# Motor_Board.net
KiCad netlist of a schematic drawn in EAGLE
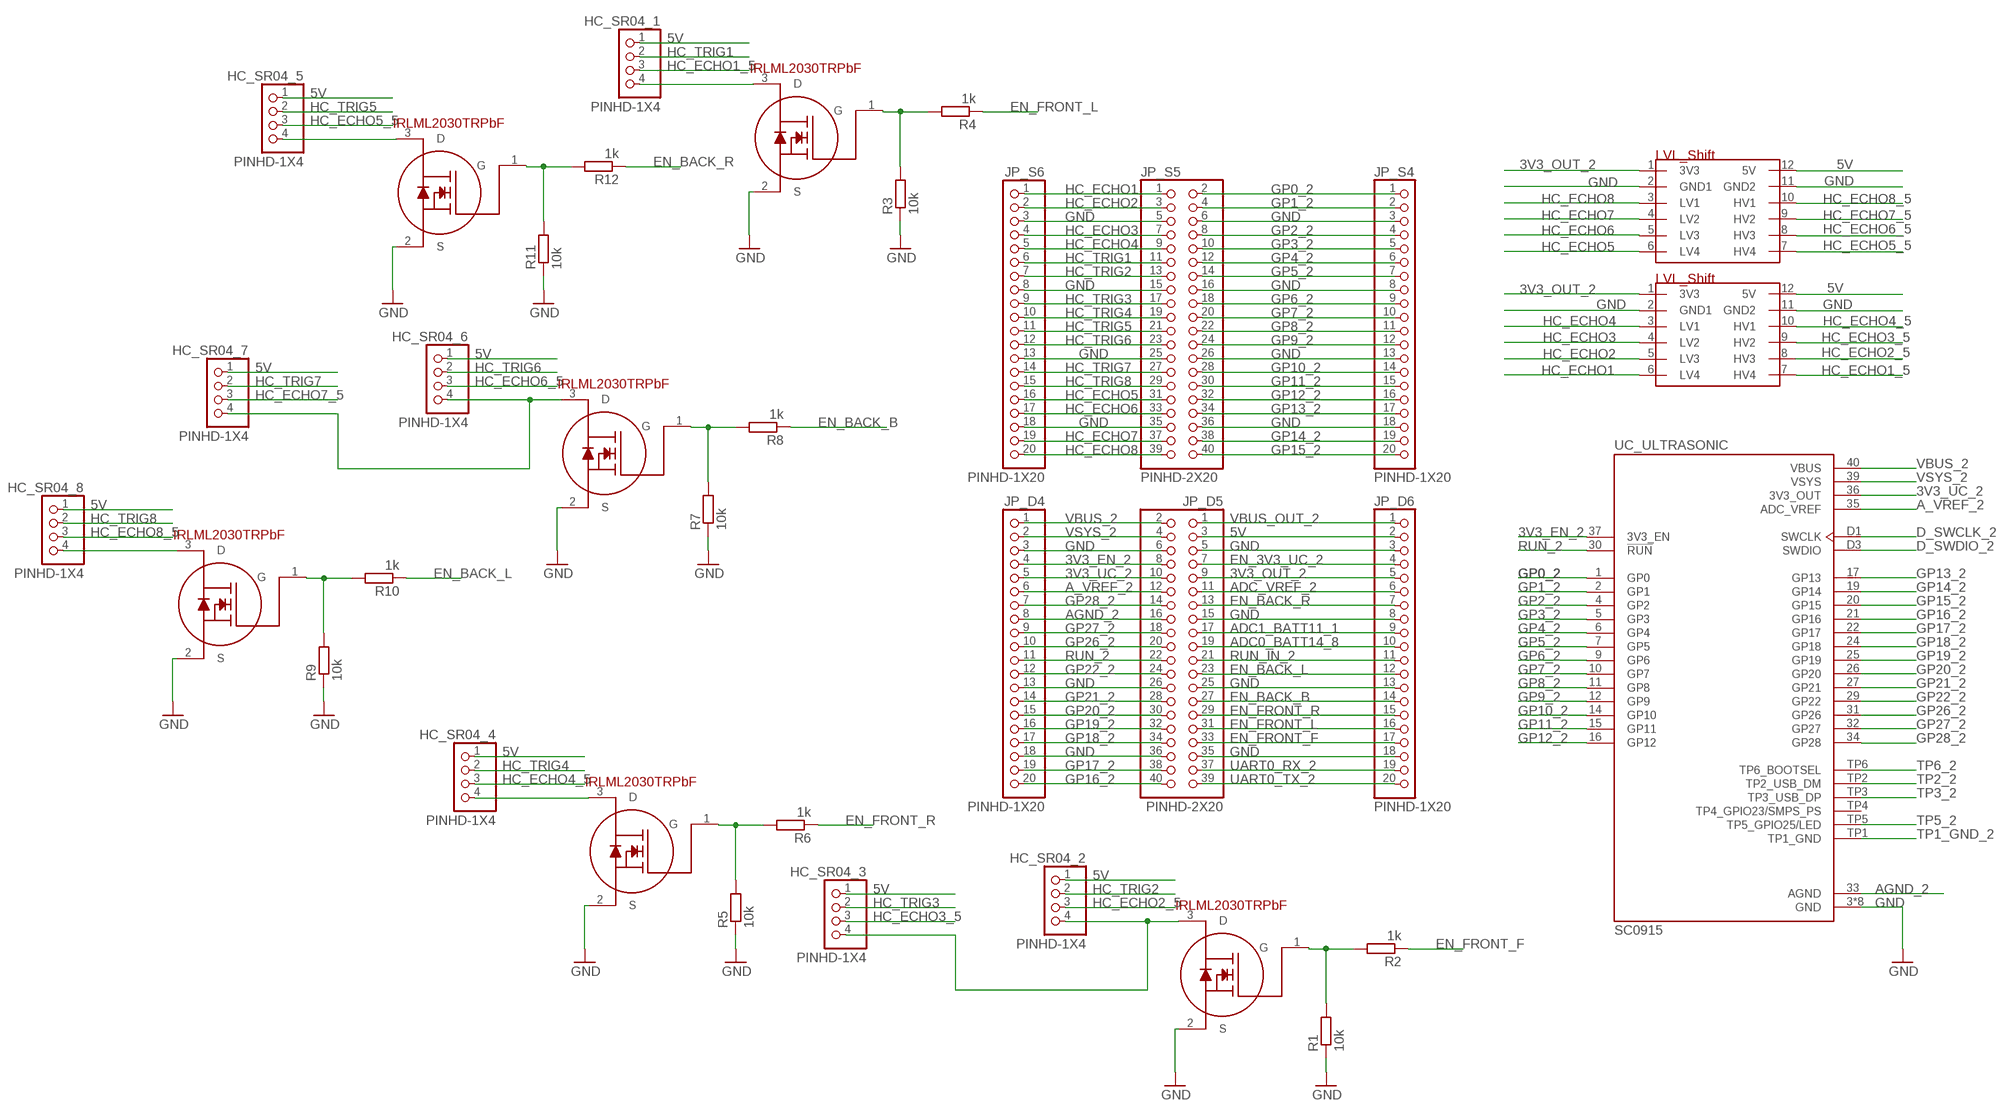
[diagram p0: schematic, sheet 1, part 1 of 2]
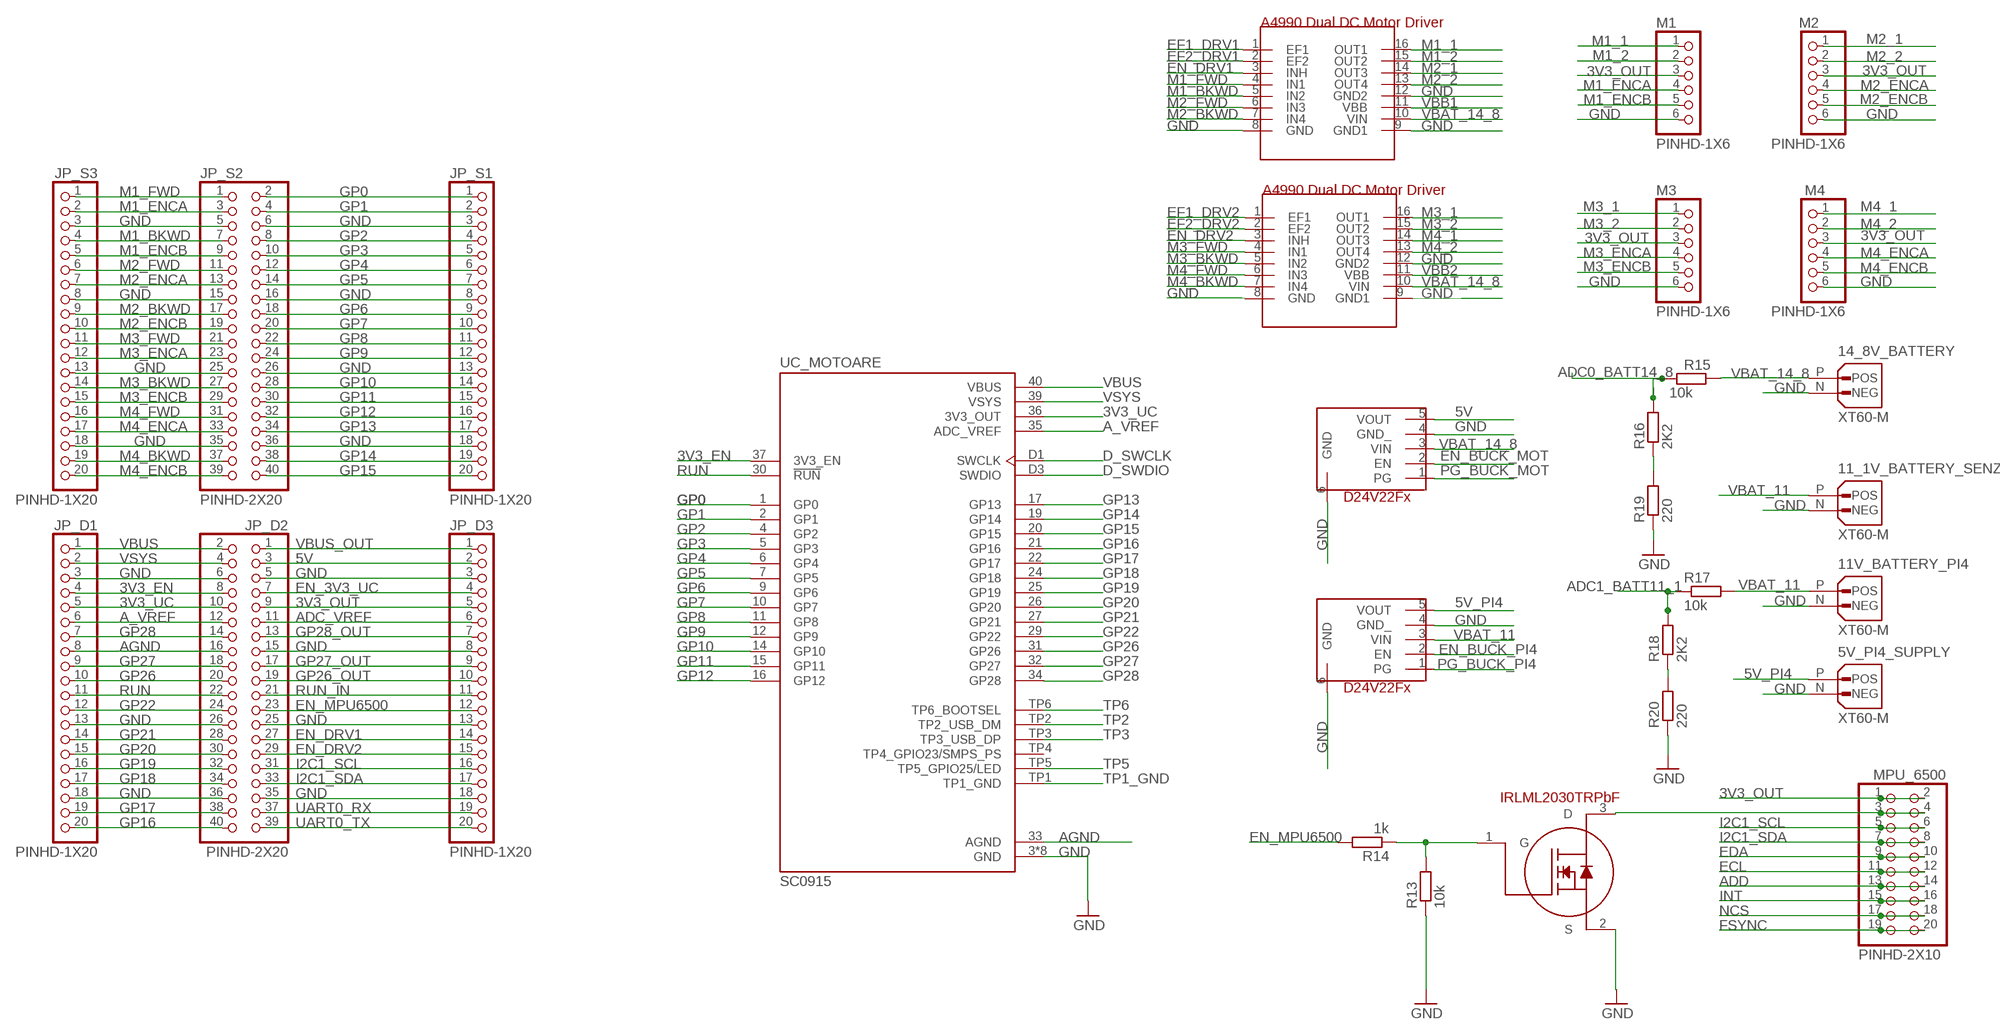
[diagram p1: schematic, sheet 1, part 2 of 2]

(export (version "E")
  (design (tool "Eeschema 10.0.6"))
  (components
    (comp (ref "5V_PI4_SUPPLY")
      (value "XT60-M")
      (footprint "eagle-import:AMASS_XT60-M")
      (fields (field (name "MANUFACTURER") "AMASS"))
      (libsource (lib "eagle-import") (part "XT60-M"))
    )
    (comp (ref "11V_BATTERY_PI4")
      (value "XT60-M")
      (footprint "eagle-import:AMASS_XT60-M")
      (fields (field (name "MANUFACTURER") "AMASS"))
      (libsource (lib "eagle-import") (part "XT60-M"))
    )
    (comp (ref "11_1V_BATTERY_SENZ")
      (value "XT60-M")
      (footprint "eagle-import:AMASS_XT60-M")
      (fields (field (name "MANUFACTURER") "AMASS"))
      (libsource (lib "eagle-import") (part "XT60-M"))
    )
    (comp (ref "14_8V_BATTERY")
      (value "XT60-M")
      (footprint "eagle-import:AMASS_XT60-M")
      (fields (field (name "MANUFACTURER") "AMASS"))
      (libsource (lib "eagle-import") (part "XT60-M"))
    )
    (comp (ref "BUCK_5V")
      (value "POLOLU_BUCK_CONVERTER")
      (footprint "eagle-import:POLOLU_BUCK_FOOTPRINT")
      (libsource (lib "eagle-import") (part "POLOLU_BUCK_CONVERTER"))
    )
    (comp (ref "BUCK_5V1")
      (value "POLOLU_BUCK_CONVERTER")
      (footprint "eagle-import:POLOLU_BUCK_FOOTPRINT")
      (libsource (lib "eagle-import") (part "POLOLU_BUCK_CONVERTER"))
    )
    (comp (ref "DRV1")
      (value "A4990_DUAL")
      (footprint "eagle-import:A4990_FOOTPRINT")
      (libsource (lib "eagle-import") (part "A4990_DUAL"))
    )
    (comp (ref "DRV2")
      (value "A4990_DUAL")
      (footprint "eagle-import:A4990_FOOTPRINT")
      (libsource (lib "eagle-import") (part "A4990_DUAL"))
    )
    (comp (ref "HC_SR04_1")
      (value "PINHD-1X4")
      (footprint "eagle-import:1X04")
      (libsource (lib "eagle-import") (part "PINHD-1X4"))
    )
    (comp (ref "HC_SR04_2")
      (value "PINHD-1X4")
      (footprint "eagle-import:1X04")
      (libsource (lib "eagle-import") (part "PINHD-1X4"))
    )
    (comp (ref "HC_SR04_3")
      (value "PINHD-1X4")
      (footprint "eagle-import:1X04")
      (libsource (lib "eagle-import") (part "PINHD-1X4"))
    )
    (comp (ref "HC_SR04_4")
      (value "PINHD-1X4")
      (footprint "eagle-import:1X04")
      (libsource (lib "eagle-import") (part "PINHD-1X4"))
    )
    (comp (ref "HC_SR04_5")
      (value "PINHD-1X4")
      (footprint "eagle-import:1X04")
      (libsource (lib "eagle-import") (part "PINHD-1X4"))
    )
    (comp (ref "HC_SR04_6")
      (value "PINHD-1X4")
      (footprint "eagle-import:1X04")
      (libsource (lib "eagle-import") (part "PINHD-1X4"))
    )
    (comp (ref "HC_SR04_7")
      (value "PINHD-1X4")
      (footprint "eagle-import:1X04")
      (libsource (lib "eagle-import") (part "PINHD-1X4"))
    )
    (comp (ref "HC_SR04_8")
      (value "PINHD-1X4")
      (footprint "eagle-import:1X04")
      (libsource (lib "eagle-import") (part "PINHD-1X4"))
    )
    (comp (ref "JP_D1")
      (value "PINHD-1X20")
      (footprint "eagle-import:1X20")
      (libsource (lib "eagle-import") (part "PINHD-1X20"))
    )
    (comp (ref "JP_D2")
      (value "PINHD-2X20")
      (footprint "eagle-import:2X20")
      (libsource (lib "eagle-import") (part "PINHD-2X20"))
    )
    (comp (ref "JP_D3")
      (value "PINHD-1X20")
      (footprint "eagle-import:1X20")
      (libsource (lib "eagle-import") (part "PINHD-1X20"))
    )
    (comp (ref "JP_D4")
      (value "PINHD-1X20")
      (footprint "eagle-import:1X20")
      (libsource (lib "eagle-import") (part "PINHD-1X20"))
    )
    (comp (ref "JP_D5")
      (value "PINHD-2X20")
      (footprint "eagle-import:2X20")
      (libsource (lib "eagle-import") (part "PINHD-2X20"))
    )
    (comp (ref "JP_D6")
      (value "PINHD-1X20")
      (footprint "eagle-import:1X20")
      (libsource (lib "eagle-import") (part "PINHD-1X20"))
    )
    (comp (ref "JP_S1")
      (value "PINHD-1X20")
      (footprint "eagle-import:1X20")
      (libsource (lib "eagle-import") (part "PINHD-1X20"))
    )
    (comp (ref "JP_S2")
      (value "PINHD-2X20")
      (footprint "eagle-import:2X20")
      (libsource (lib "eagle-import") (part "PINHD-2X20"))
    )
    (comp (ref "JP_S3")
      (value "PINHD-1X20")
      (footprint "eagle-import:1X20")
      (libsource (lib "eagle-import") (part "PINHD-1X20"))
    )
    (comp (ref "JP_S4")
      (value "PINHD-1X20")
      (footprint "eagle-import:1X20")
      (libsource (lib "eagle-import") (part "PINHD-1X20"))
    )
    (comp (ref "JP_S5")
      (value "PINHD-2X20")
      (footprint "eagle-import:2X20")
      (libsource (lib "eagle-import") (part "PINHD-2X20"))
    )
    (comp (ref "JP_S6")
      (value "PINHD-1X20")
      (footprint "eagle-import:1X20")
      (libsource (lib "eagle-import") (part "PINHD-1X20"))
    )
    (comp (ref "M1")
      (value "PINHD-1X6")
      (footprint "eagle-import:1X06")
      (libsource (lib "eagle-import") (part "PINHD-1X6"))
    )
    (comp (ref "M2")
      (value "PINHD-1X6")
      (footprint "eagle-import:1X06")
      (libsource (lib "eagle-import") (part "PINHD-1X6"))
    )
    (comp (ref "M3")
      (value "PINHD-1X6")
      (footprint "eagle-import:1X06")
      (libsource (lib "eagle-import") (part "PINHD-1X6"))
    )
    (comp (ref "M4")
      (value "PINHD-1X6")
      (footprint "eagle-import:1X06")
      (libsource (lib "eagle-import") (part "PINHD-1X6"))
    )
    (comp (ref "MPU_6500")
      (value "PINHD-2X10")
      (footprint "eagle-import:2X10")
      (libsource (lib "eagle-import") (part "PINHD-2X10"))
    )
    (comp (ref "R1")
      (value "10k")
      (footprint "eagle-import:R0805")
      (libsource (lib "eagle-import") (part "R-EU_R0805"))
    )
    (comp (ref "R2")
      (value "1k")
      (footprint "eagle-import:R0805")
      (libsource (lib "eagle-import") (part "R-EU_R0805"))
    )
    (comp (ref "R3")
      (value "10k")
      (footprint "eagle-import:R0805")
      (libsource (lib "eagle-import") (part "R-EU_R0805"))
    )
    (comp (ref "R4")
      (value "1k")
      (footprint "eagle-import:R0805")
      (libsource (lib "eagle-import") (part "R-EU_R0805"))
    )
    (comp (ref "R5")
      (value "10k")
      (footprint "eagle-import:R0805")
      (libsource (lib "eagle-import") (part "R-EU_R0805"))
    )
    (comp (ref "R6")
      (value "1k")
      (footprint "eagle-import:R0805")
      (libsource (lib "eagle-import") (part "R-EU_R0805"))
    )
    (comp (ref "R7")
      (value "10k")
      (footprint "eagle-import:R0805")
      (libsource (lib "eagle-import") (part "R-EU_R0805"))
    )
    (comp (ref "R8")
      (value "1k")
      (footprint "eagle-import:R0805")
      (libsource (lib "eagle-import") (part "R-EU_R0805"))
    )
    (comp (ref "R9")
      (value "10k")
      (footprint "eagle-import:R0805")
      (libsource (lib "eagle-import") (part "R-EU_R0805"))
    )
    (comp (ref "R10")
      (value "1k")
      (footprint "eagle-import:R0805")
      (libsource (lib "eagle-import") (part "R-EU_R0805"))
    )
    (comp (ref "R11")
      (value "10k")
      (footprint "eagle-import:R0805")
      (libsource (lib "eagle-import") (part "R-EU_R0805"))
    )
    (comp (ref "R12")
      (value "1k")
      (footprint "eagle-import:R0805")
      (libsource (lib "eagle-import") (part "R-EU_R0805"))
    )
    (comp (ref "R13")
      (value "10k")
      (footprint "eagle-import:R0805")
      (libsource (lib "eagle-import") (part "R-EU_R0805"))
    )
    (comp (ref "R14")
      (value "1k")
      (footprint "eagle-import:R0805")
      (libsource (lib "eagle-import") (part "R-EU_R0805"))
    )
    (comp (ref "R15")
      (value "10k")
      (footprint "eagle-import:R0805")
      (libsource (lib "eagle-import") (part "R-EU_R0805"))
    )
    (comp (ref "R16")
      (value "2K2")
      (footprint "eagle-import:R0805")
      (libsource (lib "eagle-import") (part "R-EU_R0805"))
    )
    (comp (ref "R17")
      (value "10k")
      (footprint "eagle-import:R0805")
      (libsource (lib "eagle-import") (part "R-EU_R0805"))
    )
    (comp (ref "R18")
      (value "2K2")
      (footprint "eagle-import:R0805")
      (libsource (lib "eagle-import") (part "R-EU_R0805"))
    )
    (comp (ref "R19")
      (value "220")
      (footprint "eagle-import:R0805")
      (libsource (lib "eagle-import") (part "R-EU_R0805"))
    )
    (comp (ref "R20")
      (value "220")
      (footprint "eagle-import:R0805")
      (libsource (lib "eagle-import") (part "R-EU_R0805"))
    )
    (comp (ref "U$1")
      (value "4_CH_BIDIRECTIONAL_LVL_SHIFTER")
      (footprint "eagle-import:LVL_SHIFT_FOOTPRINT")
      (libsource (lib "eagle-import") (part "4_CH_BIDIRECTIONAL_LVL_SHIFTER"))
    )
    (comp (ref "U$2")
      (value "4_CH_BIDIRECTIONAL_LVL_SHIFTER")
      (footprint "eagle-import:LVL_SHIFT_FOOTPRINT")
      (libsource (lib "eagle-import") (part "4_CH_BIDIRECTIONAL_LVL_SHIFTER"))
    )
    (comp (ref "U$8")
      (value "IRLML2030TRBRBF_NMOS")
      (footprint "eagle-import:IRLML2030TRPBF_FOOTPRINT")
      (libsource (lib "eagle-import") (part "IRLML2030TRBRBF_NMOS"))
    )
    (comp (ref "U$9")
      (value "IRLML2030TRBRBF_NMOS")
      (footprint "eagle-import:IRLML2030TRPBF_FOOTPRINT")
      (libsource (lib "eagle-import") (part "IRLML2030TRBRBF_NMOS"))
    )
    (comp (ref "U$10")
      (value "IRLML2030TRBRBF_NMOS")
      (footprint "eagle-import:IRLML2030TRPBF_FOOTPRINT")
      (libsource (lib "eagle-import") (part "IRLML2030TRBRBF_NMOS"))
    )
    (comp (ref "U$11")
      (value "IRLML2030TRBRBF_NMOS")
      (footprint "eagle-import:IRLML2030TRPBF_FOOTPRINT")
      (libsource (lib "eagle-import") (part "IRLML2030TRBRBF_NMOS"))
    )
    (comp (ref "U$12")
      (value "IRLML2030TRBRBF_NMOS")
      (footprint "eagle-import:IRLML2030TRPBF_FOOTPRINT")
      (libsource (lib "eagle-import") (part "IRLML2030TRBRBF_NMOS"))
    )
    (comp (ref "U$13")
      (value "IRLML2030TRBRBF_NMOS")
      (footprint "eagle-import:IRLML2030TRPBF_FOOTPRINT")
      (libsource (lib "eagle-import") (part "IRLML2030TRBRBF_NMOS"))
    )
    (comp (ref "U$14")
      (value "IRLML2030TRBRBF_NMOS")
      (footprint "eagle-import:IRLML2030TRPBF_FOOTPRINT")
      (libsource (lib "eagle-import") (part "IRLML2030TRBRBF_NMOS"))
    )
    (comp (ref "UC_MOTOARE")
      (value "SC0915")
      (footprint "eagle-import:MODULE_SC0915")
      (fields (field (name "MF") "Raspberry Pi"))
      (libsource (lib "eagle-import") (part "SC0915"))
    )
    (comp (ref "UC_ULTRASONIC")
      (value "SC0915")
      (footprint "eagle-import:MODULE_SC0915")
      (fields (field (name "MF") "Raspberry Pi"))
      (libsource (lib "eagle-import") (part "SC0915"))
    )
  )
  (nets
    (net (code "1") (name "/3V3_EN") (class "Default")
      (node (ref "JP_D1") (pin "4") (pinfunction "4_4") (pintype "passive"))
      (node (ref "JP_D2") (pin "8") (pinfunction "8_8") (pintype "passive"))
      (node (ref "UC_MOTOARE") (pin "37") (pinfunction "3V3_EN_37") (pintype "input"))
    )
    (net (code "2") (name "/3V3_EN_2") (class "Default")
      (node (ref "JP_D4") (pin "4") (pinfunction "4_4") (pintype "passive"))
      (node (ref "JP_D5") (pin "8") (pinfunction "8_8") (pintype "passive"))
      (node (ref "UC_ULTRASONIC") (pin "37") (pinfunction "3V3_EN_37") (pintype "input"))
    )
    (net (code "3") (name "/3V3_OUT") (class "Default")
      (node (ref "JP_D2") (pin "9") (pinfunction "9_9") (pintype "passive"))
      (node (ref "JP_D3") (pin "5") (pinfunction "5_5") (pintype "passive"))
      (node (ref "M1") (pin "3") (pinfunction "3_3") (pintype "passive"))
      (node (ref "M2") (pin "3") (pinfunction "3_3") (pintype "passive"))
      (node (ref "M3") (pin "3") (pinfunction "3_3") (pintype "passive"))
      (node (ref "M4") (pin "3") (pinfunction "3_3") (pintype "passive"))
      (node (ref "MPU_6500") (pin "1") (pinfunction "1_1") (pintype "passive"))
      (node (ref "MPU_6500") (pin "2") (pinfunction "2_2") (pintype "passive"))
    )
    (net (code "4") (name "/3V3_OUT_2") (class "Default")
      (node (ref "JP_D5") (pin "9") (pinfunction "9_9") (pintype "passive"))
      (node (ref "JP_D6") (pin "5") (pinfunction "5_5") (pintype "passive"))
      (node (ref "U$1") (pin "1") (pinfunction "3V3_1") (pintype "bidirectional"))
      (node (ref "U$2") (pin "1") (pinfunction "3V3_1") (pintype "bidirectional"))
    )
    (net (code "5") (name "/3V3_UC") (class "Default")
      (node (ref "JP_D1") (pin "5") (pinfunction "5_5") (pintype "passive"))
      (node (ref "JP_D2") (pin "10") (pinfunction "10_10") (pintype "passive"))
      (node (ref "UC_MOTOARE") (pin "36") (pinfunction "3V3_OUT_36") (pintype "power_in"))
    )
    (net (code "6") (name "/3V3_UC_2") (class "Default")
      (node (ref "JP_D4") (pin "5") (pinfunction "5_5") (pintype "passive"))
      (node (ref "JP_D5") (pin "10") (pinfunction "10_10") (pintype "passive"))
      (node (ref "UC_ULTRASONIC") (pin "36") (pinfunction "3V3_OUT_36") (pintype "power_in"))
    )
    (net (code "7") (name "/5V") (class "Default")
      (node (ref "BUCK_5V") (pin "5") (pinfunction "VOUT_5") (pintype "bidirectional"))
      (node (ref "HC_SR04_1") (pin "1") (pinfunction "1_1") (pintype "passive"))
      (node (ref "HC_SR04_2") (pin "1") (pinfunction "1_1") (pintype "passive"))
      (node (ref "HC_SR04_3") (pin "1") (pinfunction "1_1") (pintype "passive"))
      (node (ref "HC_SR04_4") (pin "1") (pinfunction "1_1") (pintype "passive"))
      (node (ref "HC_SR04_5") (pin "1") (pinfunction "1_1") (pintype "passive"))
      (node (ref "HC_SR04_6") (pin "1") (pinfunction "1_1") (pintype "passive"))
      (node (ref "HC_SR04_7") (pin "1") (pinfunction "1_1") (pintype "passive"))
      (node (ref "HC_SR04_8") (pin "1") (pinfunction "1_1") (pintype "passive"))
      (node (ref "JP_D2") (pin "3") (pinfunction "3_3") (pintype "passive"))
      (node (ref "JP_D3") (pin "2") (pinfunction "2_2") (pintype "passive"))
      (node (ref "JP_D5") (pin "3") (pinfunction "3_3") (pintype "passive"))
      (node (ref "JP_D6") (pin "2") (pinfunction "2_2") (pintype "passive"))
      (node (ref "U$1") (pin "12") (pinfunction "5V_12") (pintype "bidirectional"))
      (node (ref "U$2") (pin "12") (pinfunction "5V_12") (pintype "bidirectional"))
    )
    (net (code "8") (name "/5V_PI4") (class "Default")
      (node (ref "5V_PI4_SUPPLY") (pin "P") (pinfunction "POS_P") (pintype "passive"))
      (node (ref "BUCK_5V1") (pin "5") (pinfunction "VOUT_5") (pintype "bidirectional"))
    )
    (net (code "9") (name "/ADC0_BATT14_8") (class "Default")
      (node (ref "JP_D5") (pin "19") (pinfunction "19_19") (pintype "passive"))
      (node (ref "JP_D6") (pin "10") (pinfunction "10_10") (pintype "passive"))
      (node (ref "R15") (pin "1") (pinfunction "1_1") (pintype "passive"))
      (node (ref "R16") (pin "2") (pinfunction "2_2") (pintype "passive"))
    )
    (net (code "10") (name "/ADC1_BATT11_1") (class "Default")
      (node (ref "JP_D5") (pin "17") (pinfunction "17_17") (pintype "passive"))
      (node (ref "JP_D6") (pin "9") (pinfunction "9_9") (pintype "passive"))
      (node (ref "R17") (pin "1") (pinfunction "1_1") (pintype "passive"))
      (node (ref "R18") (pin "2") (pinfunction "2_2") (pintype "passive"))
    )
    (net (code "11") (name "/ADC_VREF") (class "Default")
      (node (ref "JP_D2") (pin "11") (pinfunction "11_11") (pintype "passive"))
      (node (ref "JP_D3") (pin "6") (pinfunction "6_6") (pintype "passive"))
    )
    (net (code "12") (name "/ADC_VREF_2") (class "Default")
      (node (ref "JP_D5") (pin "11") (pinfunction "11_11") (pintype "passive"))
      (node (ref "JP_D6") (pin "6") (pinfunction "6_6") (pintype "passive"))
    )
    (net (code "13") (name "/ADD") (class "Default")
      (node (ref "MPU_6500") (pin "13") (pinfunction "13_13") (pintype "passive"))
      (node (ref "MPU_6500") (pin "14") (pinfunction "14_14") (pintype "passive"))
    )
    (net (code "14") (name "/AGND") (class "Default")
      (node (ref "JP_D1") (pin "8") (pinfunction "8_8") (pintype "passive"))
      (node (ref "JP_D2") (pin "16") (pinfunction "16_16") (pintype "passive"))
      (node (ref "UC_MOTOARE") (pin "33") (pinfunction "AGND_33") (pintype "power_in"))
    )
    (net (code "15") (name "/AGND_2") (class "Default")
      (node (ref "JP_D4") (pin "8") (pinfunction "8_8") (pintype "passive"))
      (node (ref "JP_D5") (pin "16") (pinfunction "16_16") (pintype "passive"))
      (node (ref "UC_ULTRASONIC") (pin "33") (pinfunction "AGND_33") (pintype "power_in"))
    )
    (net (code "16") (name "/A_VREF") (class "Default")
      (node (ref "JP_D1") (pin "6") (pinfunction "6_6") (pintype "passive"))
      (node (ref "JP_D2") (pin "12") (pinfunction "12_12") (pintype "passive"))
      (node (ref "UC_MOTOARE") (pin "35") (pinfunction "ADC_VREF_35") (pintype "power_in"))
    )
    (net (code "17") (name "/A_VREF_2") (class "Default")
      (node (ref "JP_D4") (pin "6") (pinfunction "6_6") (pintype "passive"))
      (node (ref "JP_D5") (pin "12") (pinfunction "12_12") (pintype "passive"))
      (node (ref "UC_ULTRASONIC") (pin "35") (pinfunction "ADC_VREF_35") (pintype "power_in"))
    )
    (net (code "18") (name "/D_SWCLK") (class "Default")
      (node (ref "UC_MOTOARE") (pin "D1") (pinfunction "SWCLK_D1") (pintype "input"))
    )
    (net (code "19") (name "/D_SWCLK_2") (class "Default")
      (node (ref "UC_ULTRASONIC") (pin "D1") (pinfunction "SWCLK_D1") (pintype "input"))
    )
    (net (code "20") (name "/D_SWDIO") (class "Default")
      (node (ref "UC_MOTOARE") (pin "D3") (pinfunction "SWDIO_D3") (pintype "bidirectional"))
    )
    (net (code "21") (name "/D_SWDIO_2") (class "Default")
      (node (ref "UC_ULTRASONIC") (pin "D3") (pinfunction "SWDIO_D3") (pintype "bidirectional"))
    )
    (net (code "22") (name "/ECL") (class "Default")
      (node (ref "MPU_6500") (pin "11") (pinfunction "11_11") (pintype "passive"))
      (node (ref "MPU_6500") (pin "12") (pinfunction "12_12") (pintype "passive"))
    )
    (net (code "23") (name "/EDA") (class "Default")
      (node (ref "MPU_6500") (pin "10") (pinfunction "10_10") (pintype "passive"))
      (node (ref "MPU_6500") (pin "9") (pinfunction "9_9") (pintype "passive"))
    )
    (net (code "24") (name "/EF1_DRV1") (class "Default")
      (node (ref "DRV1") (pin "1") (pinfunction "EF1_1") (pintype "bidirectional"))
    )
    (net (code "25") (name "/EF1_DRV2") (class "Default")
      (node (ref "DRV2") (pin "1") (pinfunction "EF1_1") (pintype "bidirectional"))
    )
    (net (code "26") (name "/EF2_DRV1") (class "Default")
      (node (ref "DRV1") (pin "2") (pinfunction "EF2_2") (pintype "bidirectional"))
    )
    (net (code "27") (name "/EF2_DRV2") (class "Default")
      (node (ref "DRV2") (pin "2") (pinfunction "EF2_2") (pintype "bidirectional"))
    )
    (net (code "28") (name "/EN_3V3_UC") (class "Default")
      (node (ref "JP_D2") (pin "7") (pinfunction "7_7") (pintype "passive"))
      (node (ref "JP_D3") (pin "4") (pinfunction "4_4") (pintype "passive"))
    )
    (net (code "29") (name "/EN_3V3_UC_2") (class "Default")
      (node (ref "JP_D5") (pin "7") (pinfunction "7_7") (pintype "passive"))
      (node (ref "JP_D6") (pin "4") (pinfunction "4_4") (pintype "passive"))
    )
    (net (code "30") (name "/EN_BACK_B") (class "Default")
      (node (ref "JP_D5") (pin "27") (pinfunction "27_27") (pintype "passive"))
      (node (ref "JP_D6") (pin "14") (pinfunction "14_14") (pintype "passive"))
      (node (ref "R8") (pin "1") (pinfunction "1_1") (pintype "passive"))
    )
    (net (code "31") (name "/EN_BACK_L") (class "Default")
      (node (ref "JP_D5") (pin "23") (pinfunction "23_23") (pintype "passive"))
      (node (ref "JP_D6") (pin "12") (pinfunction "12_12") (pintype "passive"))
      (node (ref "R10") (pin "1") (pinfunction "1_1") (pintype "passive"))
    )
    (net (code "32") (name "/EN_BACK_R") (class "Default")
      (node (ref "JP_D5") (pin "13") (pinfunction "13_13") (pintype "passive"))
      (node (ref "JP_D6") (pin "7") (pinfunction "7_7") (pintype "passive"))
      (node (ref "R12") (pin "1") (pinfunction "1_1") (pintype "passive"))
    )
    (net (code "33") (name "/EN_BUCK_MOT") (class "Default")
      (node (ref "BUCK_5V") (pin "2") (pinfunction "EN_2") (pintype "bidirectional"))
    )
    (net (code "34") (name "/EN_BUCK_PI4") (class "Default")
      (node (ref "BUCK_5V1") (pin "2") (pinfunction "EN_2") (pintype "bidirectional"))
    )
    (net (code "35") (name "/EN_DRV1") (class "Default")
      (node (ref "DRV1") (pin "3") (pinfunction "INH_3") (pintype "power_in"))
      (node (ref "JP_D2") (pin "27") (pinfunction "27_27") (pintype "passive"))
      (node (ref "JP_D3") (pin "14") (pinfunction "14_14") (pintype "passive"))
    )
    (net (code "36") (name "/EN_DRV2") (class "Default")
      (node (ref "DRV2") (pin "3") (pinfunction "INH_3") (pintype "power_in"))
      (node (ref "JP_D2") (pin "29") (pinfunction "29_29") (pintype "passive"))
      (node (ref "JP_D3") (pin "15") (pinfunction "15_15") (pintype "passive"))
    )
    (net (code "37") (name "/EN_FRONT_F") (class "Default")
      (node (ref "JP_D5") (pin "33") (pinfunction "33_33") (pintype "passive"))
      (node (ref "JP_D6") (pin "17") (pinfunction "17_17") (pintype "passive"))
      (node (ref "R2") (pin "1") (pinfunction "1_1") (pintype "passive"))
    )
    (net (code "38") (name "/EN_FRONT_L") (class "Default")
      (node (ref "JP_D5") (pin "31") (pinfunction "31_31") (pintype "passive"))
      (node (ref "JP_D6") (pin "16") (pinfunction "16_16") (pintype "passive"))
      (node (ref "R4") (pin "1") (pinfunction "1_1") (pintype "passive"))
    )
    (net (code "39") (name "/EN_FRONT_R") (class "Default")
      (node (ref "JP_D5") (pin "29") (pinfunction "29_29") (pintype "passive"))
      (node (ref "JP_D6") (pin "15") (pinfunction "15_15") (pintype "passive"))
      (node (ref "R6") (pin "1") (pinfunction "1_1") (pintype "passive"))
    )
    (net (code "40") (name "/EN_MPU6500") (class "Default")
      (node (ref "JP_D2") (pin "23") (pinfunction "23_23") (pintype "passive"))
      (node (ref "JP_D3") (pin "12") (pinfunction "12_12") (pintype "passive"))
      (node (ref "R14") (pin "2") (pinfunction "2_2") (pintype "passive"))
    )
    (net (code "41") (name "/FSYNC") (class "Default")
      (node (ref "MPU_6500") (pin "19") (pinfunction "19_19") (pintype "passive"))
      (node (ref "MPU_6500") (pin "20") (pinfunction "20_20") (pintype "passive"))
    )
    (net (code "42") (name "/GP0") (class "Default")
      (node (ref "JP_S1") (pin "1") (pinfunction "1_1") (pintype "passive"))
      (node (ref "JP_S2") (pin "2") (pinfunction "2_2") (pintype "passive"))
      (node (ref "UC_MOTOARE") (pin "1") (pinfunction "GP0_1") (pintype "bidirectional"))
    )
    (net (code "43") (name "/GP0_2") (class "Default")
      (node (ref "JP_S4") (pin "1") (pinfunction "1_1") (pintype "passive"))
      (node (ref "JP_S5") (pin "2") (pinfunction "2_2") (pintype "passive"))
      (node (ref "UC_ULTRASONIC") (pin "1") (pinfunction "GP0_1") (pintype "bidirectional"))
    )
    (net (code "44") (name "/GP1") (class "Default")
      (node (ref "JP_S1") (pin "2") (pinfunction "2_2") (pintype "passive"))
      (node (ref "JP_S2") (pin "4") (pinfunction "4_4") (pintype "passive"))
      (node (ref "UC_MOTOARE") (pin "2") (pinfunction "GP1_2") (pintype "bidirectional"))
    )
    (net (code "45") (name "/GP1_2") (class "Default")
      (node (ref "JP_S4") (pin "2") (pinfunction "2_2") (pintype "passive"))
      (node (ref "JP_S5") (pin "4") (pinfunction "4_4") (pintype "passive"))
      (node (ref "UC_ULTRASONIC") (pin "2") (pinfunction "GP1_2") (pintype "bidirectional"))
    )
    (net (code "46") (name "/GP2") (class "Default")
      (node (ref "JP_S1") (pin "4") (pinfunction "4_4") (pintype "passive"))
      (node (ref "JP_S2") (pin "8") (pinfunction "8_8") (pintype "passive"))
      (node (ref "UC_MOTOARE") (pin "4") (pinfunction "GP2_4") (pintype "bidirectional"))
    )
    (net (code "47") (name "/GP2_2") (class "Default")
      (node (ref "JP_S4") (pin "4") (pinfunction "4_4") (pintype "passive"))
      (node (ref "JP_S5") (pin "8") (pinfunction "8_8") (pintype "passive"))
      (node (ref "UC_ULTRASONIC") (pin "4") (pinfunction "GP2_4") (pintype "bidirectional"))
    )
    (net (code "48") (name "/GP3") (class "Default")
      (node (ref "JP_S1") (pin "5") (pinfunction "5_5") (pintype "passive"))
      (node (ref "JP_S2") (pin "10") (pinfunction "10_10") (pintype "passive"))
      (node (ref "UC_MOTOARE") (pin "5") (pinfunction "GP3_5") (pintype "bidirectional"))
    )
    (net (code "49") (name "/GP3_2") (class "Default")
      (node (ref "JP_S4") (pin "5") (pinfunction "5_5") (pintype "passive"))
      (node (ref "JP_S5") (pin "10") (pinfunction "10_10") (pintype "passive"))
      (node (ref "UC_ULTRASONIC") (pin "5") (pinfunction "GP3_5") (pintype "bidirectional"))
    )
    (net (code "50") (name "/GP4") (class "Default")
      (node (ref "JP_S1") (pin "6") (pinfunction "6_6") (pintype "passive"))
      (node (ref "JP_S2") (pin "12") (pinfunction "12_12") (pintype "passive"))
      (node (ref "UC_MOTOARE") (pin "6") (pinfunction "GP4_6") (pintype "bidirectional"))
    )
    (net (code "51") (name "/GP4_2") (class "Default")
      (node (ref "JP_S4") (pin "6") (pinfunction "6_6") (pintype "passive"))
      (node (ref "JP_S5") (pin "12") (pinfunction "12_12") (pintype "passive"))
      (node (ref "UC_ULTRASONIC") (pin "6") (pinfunction "GP4_6") (pintype "bidirectional"))
    )
    (net (code "52") (name "/GP5") (class "Default")
      (node (ref "JP_S1") (pin "7") (pinfunction "7_7") (pintype "passive"))
      (node (ref "JP_S2") (pin "14") (pinfunction "14_14") (pintype "passive"))
      (node (ref "UC_MOTOARE") (pin "7") (pinfunction "GP5_7") (pintype "bidirectional"))
    )
    (net (code "53") (name "/GP5_2") (class "Default")
      (node (ref "JP_S4") (pin "7") (pinfunction "7_7") (pintype "passive"))
      (node (ref "JP_S5") (pin "14") (pinfunction "14_14") (pintype "passive"))
      (node (ref "UC_ULTRASONIC") (pin "7") (pinfunction "GP5_7") (pintype "bidirectional"))
    )
    (net (code "54") (name "/GP6") (class "Default")
      (node (ref "JP_S1") (pin "9") (pinfunction "9_9") (pintype "passive"))
      (node (ref "JP_S2") (pin "18") (pinfunction "18_18") (pintype "passive"))
      (node (ref "UC_MOTOARE") (pin "9") (pinfunction "GP6_9") (pintype "bidirectional"))
    )
    (net (code "55") (name "/GP6_2") (class "Default")
      (node (ref "JP_S4") (pin "9") (pinfunction "9_9") (pintype "passive"))
      (node (ref "JP_S5") (pin "18") (pinfunction "18_18") (pintype "passive"))
      (node (ref "UC_ULTRASONIC") (pin "9") (pinfunction "GP6_9") (pintype "bidirectional"))
    )
    (net (code "56") (name "/GP7") (class "Default")
      (node (ref "JP_S1") (pin "10") (pinfunction "10_10") (pintype "passive"))
      (node (ref "JP_S2") (pin "20") (pinfunction "20_20") (pintype "passive"))
      (node (ref "UC_MOTOARE") (pin "10") (pinfunction "GP7_10") (pintype "bidirectional"))
    )
    (net (code "57") (name "/GP7_2") (class "Default")
      (node (ref "JP_S4") (pin "10") (pinfunction "10_10") (pintype "passive"))
      (node (ref "JP_S5") (pin "20") (pinfunction "20_20") (pintype "passive"))
      (node (ref "UC_ULTRASONIC") (pin "10") (pinfunction "GP7_10") (pintype "bidirectional"))
    )
    (net (code "58") (name "/GP8") (class "Default")
      (node (ref "JP_S1") (pin "11") (pinfunction "11_11") (pintype "passive"))
      (node (ref "JP_S2") (pin "22") (pinfunction "22_22") (pintype "passive"))
      (node (ref "UC_MOTOARE") (pin "11") (pinfunction "GP8_11") (pintype "bidirectional"))
    )
    (net (code "59") (name "/GP8_2") (class "Default")
      (node (ref "JP_S4") (pin "11") (pinfunction "11_11") (pintype "passive"))
      (node (ref "JP_S5") (pin "22") (pinfunction "22_22") (pintype "passive"))
      (node (ref "UC_ULTRASONIC") (pin "11") (pinfunction "GP8_11") (pintype "bidirectional"))
    )
    (net (code "60") (name "/GP9") (class "Default")
      (node (ref "JP_S1") (pin "12") (pinfunction "12_12") (pintype "passive"))
      (node (ref "JP_S2") (pin "24") (pinfunction "24_24") (pintype "passive"))
      (node (ref "UC_MOTOARE") (pin "12") (pinfunction "GP9_12") (pintype "bidirectional"))
    )
    (net (code "61") (name "/GP9_2") (class "Default")
      (node (ref "JP_S4") (pin "12") (pinfunction "12_12") (pintype "passive"))
      (node (ref "JP_S5") (pin "24") (pinfunction "24_24") (pintype "passive"))
      (node (ref "UC_ULTRASONIC") (pin "12") (pinfunction "GP9_12") (pintype "bidirectional"))
    )
    (net (code "62") (name "/GP10") (class "Default")
      (node (ref "JP_S1") (pin "14") (pinfunction "14_14") (pintype "passive"))
      (node (ref "JP_S2") (pin "28") (pinfunction "28_28") (pintype "passive"))
      (node (ref "UC_MOTOARE") (pin "14") (pinfunction "GP10_14") (pintype "bidirectional"))
    )
    (net (code "63") (name "/GP10_2") (class "Default")
      (node (ref "JP_S4") (pin "14") (pinfunction "14_14") (pintype "passive"))
      (node (ref "JP_S5") (pin "28") (pinfunction "28_28") (pintype "passive"))
      (node (ref "UC_ULTRASONIC") (pin "14") (pinfunction "GP10_14") (pintype "bidirectional"))
    )
    (net (code "64") (name "/GP11") (class "Default")
      (node (ref "JP_S1") (pin "15") (pinfunction "15_15") (pintype "passive"))
      (node (ref "JP_S2") (pin "30") (pinfunction "30_30") (pintype "passive"))
      (node (ref "UC_MOTOARE") (pin "15") (pinfunction "GP11_15") (pintype "bidirectional"))
    )
    (net (code "65") (name "/GP11_2") (class "Default")
      (node (ref "JP_S4") (pin "15") (pinfunction "15_15") (pintype "passive"))
      (node (ref "JP_S5") (pin "30") (pinfunction "30_30") (pintype "passive"))
      (node (ref "UC_ULTRASONIC") (pin "15") (pinfunction "GP11_15") (pintype "bidirectional"))
    )
    (net (code "66") (name "/GP12") (class "Default")
      (node (ref "JP_S1") (pin "16") (pinfunction "16_16") (pintype "passive"))
      (node (ref "JP_S2") (pin "32") (pinfunction "32_32") (pintype "passive"))
      (node (ref "UC_MOTOARE") (pin "16") (pinfunction "GP12_16") (pintype "bidirectional"))
    )
    (net (code "67") (name "/GP12_2") (class "Default")
      (node (ref "JP_S4") (pin "16") (pinfunction "16_16") (pintype "passive"))
      (node (ref "JP_S5") (pin "32") (pinfunction "32_32") (pintype "passive"))
      (node (ref "UC_ULTRASONIC") (pin "16") (pinfunction "GP12_16") (pintype "bidirectional"))
    )
    (net (code "68") (name "/GP13") (class "Default")
      (node (ref "JP_S1") (pin "17") (pinfunction "17_17") (pintype "passive"))
      (node (ref "JP_S2") (pin "34") (pinfunction "34_34") (pintype "passive"))
      (node (ref "UC_MOTOARE") (pin "17") (pinfunction "GP13_17") (pintype "bidirectional"))
    )
    (net (code "69") (name "/GP13_2") (class "Default")
      (node (ref "JP_S4") (pin "17") (pinfunction "17_17") (pintype "passive"))
      (node (ref "JP_S5") (pin "34") (pinfunction "34_34") (pintype "passive"))
      (node (ref "UC_ULTRASONIC") (pin "17") (pinfunction "GP13_17") (pintype "bidirectional"))
    )
    (net (code "70") (name "/GP14") (class "Default")
      (node (ref "JP_S1") (pin "19") (pinfunction "19_19") (pintype "passive"))
      (node (ref "JP_S2") (pin "38") (pinfunction "38_38") (pintype "passive"))
      (node (ref "UC_MOTOARE") (pin "19") (pinfunction "GP14_19") (pintype "bidirectional"))
    )
    (net (code "71") (name "/GP14_2") (class "Default")
      (node (ref "JP_S4") (pin "19") (pinfunction "19_19") (pintype "passive"))
      (node (ref "JP_S5") (pin "38") (pinfunction "38_38") (pintype "passive"))
      (node (ref "UC_ULTRASONIC") (pin "19") (pinfunction "GP14_19") (pintype "bidirectional"))
    )
    (net (code "72") (name "/GP15") (class "Default")
      (node (ref "JP_S1") (pin "20") (pinfunction "20_20") (pintype "passive"))
      (node (ref "JP_S2") (pin "40") (pinfunction "40_40") (pintype "passive"))
      (node (ref "UC_MOTOARE") (pin "20") (pinfunction "GP15_20") (pintype "bidirectional"))
    )
    (net (code "73") (name "/GP15_2") (class "Default")
      (node (ref "JP_S4") (pin "20") (pinfunction "20_20") (pintype "passive"))
      (node (ref "JP_S5") (pin "40") (pinfunction "40_40") (pintype "passive"))
      (node (ref "UC_ULTRASONIC") (pin "20") (pinfunction "GP15_20") (pintype "bidirectional"))
    )
    (net (code "74") (name "/GP16") (class "Default")
      (node (ref "JP_D1") (pin "20") (pinfunction "20_20") (pintype "passive"))
      (node (ref "JP_D2") (pin "40") (pinfunction "40_40") (pintype "passive"))
      (node (ref "UC_MOTOARE") (pin "21") (pinfunction "GP16_21") (pintype "bidirectional"))
    )
    (net (code "75") (name "/GP16_2") (class "Default")
      (node (ref "JP_D4") (pin "20") (pinfunction "20_20") (pintype "passive"))
      (node (ref "JP_D5") (pin "40") (pinfunction "40_40") (pintype "passive"))
      (node (ref "UC_ULTRASONIC") (pin "21") (pinfunction "GP16_21") (pintype "bidirectional"))
    )
    (net (code "76") (name "/GP17") (class "Default")
      (node (ref "JP_D1") (pin "19") (pinfunction "19_19") (pintype "passive"))
      (node (ref "JP_D2") (pin "38") (pinfunction "38_38") (pintype "passive"))
      (node (ref "UC_MOTOARE") (pin "22") (pinfunction "GP17_22") (pintype "bidirectional"))
    )
    (net (code "77") (name "/GP17_2") (class "Default")
      (node (ref "JP_D4") (pin "19") (pinfunction "19_19") (pintype "passive"))
      (node (ref "JP_D5") (pin "38") (pinfunction "38_38") (pintype "passive"))
      (node (ref "UC_ULTRASONIC") (pin "22") (pinfunction "GP17_22") (pintype "bidirectional"))
    )
    (net (code "78") (name "/GP18") (class "Default")
      (node (ref "JP_D1") (pin "17") (pinfunction "17_17") (pintype "passive"))
      (node (ref "JP_D2") (pin "34") (pinfunction "34_34") (pintype "passive"))
      (node (ref "UC_MOTOARE") (pin "24") (pinfunction "GP18_24") (pintype "bidirectional"))
    )
    (net (code "79") (name "/GP18_2") (class "Default")
      (node (ref "JP_D4") (pin "17") (pinfunction "17_17") (pintype "passive"))
      (node (ref "JP_D5") (pin "34") (pinfunction "34_34") (pintype "passive"))
      (node (ref "UC_ULTRASONIC") (pin "24") (pinfunction "GP18_24") (pintype "bidirectional"))
    )
    (net (code "80") (name "/GP19") (class "Default")
      (node (ref "JP_D1") (pin "16") (pinfunction "16_16") (pintype "passive"))
      (node (ref "JP_D2") (pin "32") (pinfunction "32_32") (pintype "passive"))
      (node (ref "UC_MOTOARE") (pin "25") (pinfunction "GP19_25") (pintype "bidirectional"))
    )
    (net (code "81") (name "/GP19_2") (class "Default")
      (node (ref "JP_D4") (pin "16") (pinfunction "16_16") (pintype "passive"))
      (node (ref "JP_D5") (pin "32") (pinfunction "32_32") (pintype "passive"))
      (node (ref "UC_ULTRASONIC") (pin "25") (pinfunction "GP19_25") (pintype "bidirectional"))
    )
    (net (code "82") (name "/GP20") (class "Default")
      (node (ref "JP_D1") (pin "15") (pinfunction "15_15") (pintype "passive"))
      (node (ref "JP_D2") (pin "30") (pinfunction "30_30") (pintype "passive"))
      (node (ref "UC_MOTOARE") (pin "26") (pinfunction "GP20_26") (pintype "bidirectional"))
    )
    (net (code "83") (name "/GP20_2") (class "Default")
      (node (ref "JP_D4") (pin "15") (pinfunction "15_15") (pintype "passive"))
      (node (ref "JP_D5") (pin "30") (pinfunction "30_30") (pintype "passive"))
      (node (ref "UC_ULTRASONIC") (pin "26") (pinfunction "GP20_26") (pintype "bidirectional"))
    )
    (net (code "84") (name "/GP21") (class "Default")
      (node (ref "JP_D1") (pin "14") (pinfunction "14_14") (pintype "passive"))
      (node (ref "JP_D2") (pin "28") (pinfunction "28_28") (pintype "passive"))
      (node (ref "UC_MOTOARE") (pin "27") (pinfunction "GP21_27") (pintype "bidirectional"))
    )
    (net (code "85") (name "/GP21_2") (class "Default")
      (node (ref "JP_D4") (pin "14") (pinfunction "14_14") (pintype "passive"))
      (node (ref "JP_D5") (pin "28") (pinfunction "28_28") (pintype "passive"))
      (node (ref "UC_ULTRASONIC") (pin "27") (pinfunction "GP21_27") (pintype "bidirectional"))
    )
    (net (code "86") (name "/GP22") (class "Default")
      (node (ref "JP_D1") (pin "12") (pinfunction "12_12") (pintype "passive"))
      (node (ref "JP_D2") (pin "24") (pinfunction "24_24") (pintype "passive"))
      (node (ref "UC_MOTOARE") (pin "29") (pinfunction "GP22_29") (pintype "bidirectional"))
    )
    (net (code "87") (name "/GP22_2") (class "Default")
      (node (ref "JP_D4") (pin "12") (pinfunction "12_12") (pintype "passive"))
      (node (ref "JP_D5") (pin "24") (pinfunction "24_24") (pintype "passive"))
      (node (ref "UC_ULTRASONIC") (pin "29") (pinfunction "GP22_29") (pintype "bidirectional"))
    )
    (net (code "88") (name "/GP26") (class "Default")
      (node (ref "JP_D1") (pin "10") (pinfunction "10_10") (pintype "passive"))
      (node (ref "JP_D2") (pin "20") (pinfunction "20_20") (pintype "passive"))
      (node (ref "UC_MOTOARE") (pin "31") (pinfunction "GP26_31") (pintype "bidirectional"))
    )
    (net (code "89") (name "/GP26_2") (class "Default")
      (node (ref "JP_D4") (pin "10") (pinfunction "10_10") (pintype "passive"))
      (node (ref "JP_D5") (pin "20") (pinfunction "20_20") (pintype "passive"))
      (node (ref "UC_ULTRASONIC") (pin "31") (pinfunction "GP26_31") (pintype "bidirectional"))
    )
    (net (code "90") (name "/GP26_OUT") (class "Default")
      (node (ref "JP_D2") (pin "19") (pinfunction "19_19") (pintype "passive"))
      (node (ref "JP_D3") (pin "10") (pinfunction "10_10") (pintype "passive"))
    )
    (net (code "91") (name "/GP27") (class "Default")
      (node (ref "JP_D1") (pin "9") (pinfunction "9_9") (pintype "passive"))
      (node (ref "JP_D2") (pin "18") (pinfunction "18_18") (pintype "passive"))
      (node (ref "UC_MOTOARE") (pin "32") (pinfunction "GP27_32") (pintype "bidirectional"))
    )
    (net (code "92") (name "/GP27_2") (class "Default")
      (node (ref "JP_D4") (pin "9") (pinfunction "9_9") (pintype "passive"))
      (node (ref "JP_D5") (pin "18") (pinfunction "18_18") (pintype "passive"))
      (node (ref "UC_ULTRASONIC") (pin "32") (pinfunction "GP27_32") (pintype "bidirectional"))
    )
    (net (code "93") (name "/GP27_OUT") (class "Default")
      (node (ref "JP_D2") (pin "17") (pinfunction "17_17") (pintype "passive"))
      (node (ref "JP_D3") (pin "9") (pinfunction "9_9") (pintype "passive"))
    )
    (net (code "94") (name "/GP28") (class "Default")
      (node (ref "JP_D1") (pin "7") (pinfunction "7_7") (pintype "passive"))
      (node (ref "JP_D2") (pin "14") (pinfunction "14_14") (pintype "passive"))
      (node (ref "UC_MOTOARE") (pin "34") (pinfunction "GP28_34") (pintype "bidirectional"))
    )
    (net (code "95") (name "/GP28_2") (class "Default")
      (node (ref "JP_D4") (pin "7") (pinfunction "7_7") (pintype "passive"))
      (node (ref "JP_D5") (pin "14") (pinfunction "14_14") (pintype "passive"))
      (node (ref "UC_ULTRASONIC") (pin "34") (pinfunction "GP28_34") (pintype "bidirectional"))
    )
    (net (code "96") (name "/GP28_OUT") (class "Default")
      (node (ref "JP_D2") (pin "13") (pinfunction "13_13") (pintype "passive"))
      (node (ref "JP_D3") (pin "7") (pinfunction "7_7") (pintype "passive"))
    )
    (net (code "97") (name "/HC_ECHO1") (class "Default")
      (node (ref "JP_S5") (pin "1") (pinfunction "1_1") (pintype "passive"))
      (node (ref "JP_S6") (pin "1") (pinfunction "1_1") (pintype "passive"))
      (node (ref "U$2") (pin "6") (pinfunction "LV4_6") (pintype "bidirectional"))
    )
    (net (code "98") (name "/HC_ECHO1_5") (class "Default")
      (node (ref "HC_SR04_1") (pin "3") (pinfunction "3_3") (pintype "passive"))
      (node (ref "U$2") (pin "7") (pinfunction "HV4_7") (pintype "bidirectional"))
    )
    (net (code "99") (name "/HC_ECHO2") (class "Default")
      (node (ref "JP_S5") (pin "3") (pinfunction "3_3") (pintype "passive"))
      (node (ref "JP_S6") (pin "2") (pinfunction "2_2") (pintype "passive"))
      (node (ref "U$2") (pin "5") (pinfunction "LV3_5") (pintype "bidirectional"))
    )
    (net (code "100") (name "/HC_ECHO2_5") (class "Default")
      (node (ref "HC_SR04_2") (pin "3") (pinfunction "3_3") (pintype "passive"))
      (node (ref "U$2") (pin "8") (pinfunction "HV3_8") (pintype "bidirectional"))
    )
    (net (code "101") (name "/HC_ECHO3") (class "Default")
      (node (ref "JP_S5") (pin "7") (pinfunction "7_7") (pintype "passive"))
      (node (ref "JP_S6") (pin "4") (pinfunction "4_4") (pintype "passive"))
      (node (ref "U$2") (pin "4") (pinfunction "LV2_4") (pintype "bidirectional"))
    )
    (net (code "102") (name "/HC_ECHO3_5") (class "Default")
      (node (ref "HC_SR04_3") (pin "3") (pinfunction "3_3") (pintype "passive"))
      (node (ref "U$2") (pin "9") (pinfunction "HV2_9") (pintype "bidirectional"))
    )
    (net (code "103") (name "/HC_ECHO4") (class "Default")
      (node (ref "JP_S5") (pin "9") (pinfunction "9_9") (pintype "passive"))
      (node (ref "JP_S6") (pin "5") (pinfunction "5_5") (pintype "passive"))
      (node (ref "U$2") (pin "3") (pinfunction "LV1_3") (pintype "bidirectional"))
    )
    (net (code "104") (name "/HC_ECHO4_5") (class "Default")
      (node (ref "HC_SR04_4") (pin "3") (pinfunction "3_3") (pintype "passive"))
      (node (ref "U$2") (pin "10") (pinfunction "HV1_10") (pintype "bidirectional"))
    )
    (net (code "105") (name "/HC_ECHO5") (class "Default")
      (node (ref "JP_S5") (pin "31") (pinfunction "31_31") (pintype "passive"))
      (node (ref "JP_S6") (pin "16") (pinfunction "16_16") (pintype "passive"))
      (node (ref "U$1") (pin "6") (pinfunction "LV4_6") (pintype "bidirectional"))
    )
    (net (code "106") (name "/HC_ECHO5_5") (class "Default")
      (node (ref "HC_SR04_5") (pin "3") (pinfunction "3_3") (pintype "passive"))
      (node (ref "U$1") (pin "7") (pinfunction "HV4_7") (pintype "bidirectional"))
    )
    (net (code "107") (name "/HC_ECHO6") (class "Default")
      (node (ref "JP_S5") (pin "33") (pinfunction "33_33") (pintype "passive"))
      (node (ref "JP_S6") (pin "17") (pinfunction "17_17") (pintype "passive"))
      (node (ref "U$1") (pin "5") (pinfunction "LV3_5") (pintype "bidirectional"))
    )
    (net (code "108") (name "/HC_ECHO6_5") (class "Default")
      (node (ref "HC_SR04_6") (pin "3") (pinfunction "3_3") (pintype "passive"))
      (node (ref "U$1") (pin "8") (pinfunction "HV3_8") (pintype "bidirectional"))
    )
    (net (code "109") (name "/HC_ECHO7") (class "Default")
      (node (ref "JP_S5") (pin "37") (pinfunction "37_37") (pintype "passive"))
      (node (ref "JP_S6") (pin "19") (pinfunction "19_19") (pintype "passive"))
      (node (ref "U$1") (pin "4") (pinfunction "LV2_4") (pintype "bidirectional"))
    )
    (net (code "110") (name "/HC_ECHO7_5") (class "Default")
      (node (ref "HC_SR04_7") (pin "3") (pinfunction "3_3") (pintype "passive"))
      (node (ref "U$1") (pin "9") (pinfunction "HV2_9") (pintype "bidirectional"))
    )
    (net (code "111") (name "/HC_ECHO8") (class "Default")
      (node (ref "JP_S5") (pin "39") (pinfunction "39_39") (pintype "passive"))
      (node (ref "JP_S6") (pin "20") (pinfunction "20_20") (pintype "passive"))
      (node (ref "U$1") (pin "3") (pinfunction "LV1_3") (pintype "bidirectional"))
    )
    (net (code "112") (name "/HC_ECHO8_5") (class "Default")
      (node (ref "HC_SR04_8") (pin "3") (pinfunction "3_3") (pintype "passive"))
      (node (ref "U$1") (pin "10") (pinfunction "HV1_10") (pintype "bidirectional"))
    )
    (net (code "113") (name "/HC_TRIG1") (class "Default")
      (node (ref "HC_SR04_1") (pin "2") (pinfunction "2_2") (pintype "passive"))
      (node (ref "JP_S5") (pin "11") (pinfunction "11_11") (pintype "passive"))
      (node (ref "JP_S6") (pin "6") (pinfunction "6_6") (pintype "passive"))
    )
    (net (code "114") (name "/HC_TRIG2") (class "Default")
      (node (ref "HC_SR04_2") (pin "2") (pinfunction "2_2") (pintype "passive"))
      (node (ref "JP_S5") (pin "13") (pinfunction "13_13") (pintype "passive"))
      (node (ref "JP_S6") (pin "7") (pinfunction "7_7") (pintype "passive"))
    )
    (net (code "115") (name "/HC_TRIG3") (class "Default")
      (node (ref "HC_SR04_3") (pin "2") (pinfunction "2_2") (pintype "passive"))
      (node (ref "JP_S5") (pin "17") (pinfunction "17_17") (pintype "passive"))
      (node (ref "JP_S6") (pin "9") (pinfunction "9_9") (pintype "passive"))
    )
    (net (code "116") (name "/HC_TRIG4") (class "Default")
      (node (ref "HC_SR04_4") (pin "2") (pinfunction "2_2") (pintype "passive"))
      (node (ref "JP_S5") (pin "19") (pinfunction "19_19") (pintype "passive"))
      (node (ref "JP_S6") (pin "10") (pinfunction "10_10") (pintype "passive"))
    )
    (net (code "117") (name "/HC_TRIG5") (class "Default")
      (node (ref "HC_SR04_5") (pin "2") (pinfunction "2_2") (pintype "passive"))
      (node (ref "JP_S5") (pin "21") (pinfunction "21_21") (pintype "passive"))
      (node (ref "JP_S6") (pin "11") (pinfunction "11_11") (pintype "passive"))
    )
    (net (code "118") (name "/HC_TRIG6") (class "Default")
      (node (ref "HC_SR04_6") (pin "2") (pinfunction "2_2") (pintype "passive"))
      (node (ref "JP_S5") (pin "23") (pinfunction "23_23") (pintype "passive"))
      (node (ref "JP_S6") (pin "12") (pinfunction "12_12") (pintype "passive"))
    )
    (net (code "119") (name "/HC_TRIG7") (class "Default")
      (node (ref "HC_SR04_7") (pin "2") (pinfunction "2_2") (pintype "passive"))
      (node (ref "JP_S5") (pin "27") (pinfunction "27_27") (pintype "passive"))
      (node (ref "JP_S6") (pin "14") (pinfunction "14_14") (pintype "passive"))
    )
    (net (code "120") (name "/HC_TRIG8") (class "Default")
      (node (ref "HC_SR04_8") (pin "2") (pinfunction "2_2") (pintype "passive"))
      (node (ref "JP_S5") (pin "29") (pinfunction "29_29") (pintype "passive"))
      (node (ref "JP_S6") (pin "15") (pinfunction "15_15") (pintype "passive"))
    )
    (net (code "121") (name "/I2C1_SCL") (class "Default")
      (node (ref "JP_D2") (pin "31") (pinfunction "31_31") (pintype "passive"))
      (node (ref "JP_D3") (pin "16") (pinfunction "16_16") (pintype "passive"))
      (node (ref "MPU_6500") (pin "5") (pinfunction "5_5") (pintype "passive"))
      (node (ref "MPU_6500") (pin "6") (pinfunction "6_6") (pintype "passive"))
    )
    (net (code "122") (name "/I2C1_SDA") (class "Default")
      (node (ref "JP_D2") (pin "33") (pinfunction "33_33") (pintype "passive"))
      (node (ref "JP_D3") (pin "17") (pinfunction "17_17") (pintype "passive"))
      (node (ref "MPU_6500") (pin "7") (pinfunction "7_7") (pintype "passive"))
      (node (ref "MPU_6500") (pin "8") (pinfunction "8_8") (pintype "passive"))
    )
    (net (code "123") (name "/INT") (class "Default")
      (node (ref "MPU_6500") (pin "15") (pinfunction "15_15") (pintype "passive"))
      (node (ref "MPU_6500") (pin "16") (pinfunction "16_16") (pintype "passive"))
    )
    (net (code "124") (name "/M1_1") (class "Default")
      (node (ref "DRV1") (pin "16") (pinfunction "OUT1_16") (pintype "output"))
      (node (ref "M1") (pin "1") (pinfunction "1_1") (pintype "passive"))
    )
    (net (code "125") (name "/M1_2") (class "Default")
      (node (ref "DRV1") (pin "15") (pinfunction "OUT2_15") (pintype "output"))
      (node (ref "M1") (pin "2") (pinfunction "2_2") (pintype "passive"))
    )
    (net (code "126") (name "/M1_BKWD") (class "Default")
      (node (ref "DRV1") (pin "5") (pinfunction "IN2_5") (pintype "input"))
      (node (ref "JP_S2") (pin "7") (pinfunction "7_7") (pintype "passive"))
      (node (ref "JP_S3") (pin "4") (pinfunction "4_4") (pintype "passive"))
    )
    (net (code "127") (name "/M1_ENCA") (class "Default")
      (node (ref "JP_S2") (pin "3") (pinfunction "3_3") (pintype "passive"))
      (node (ref "JP_S3") (pin "2") (pinfunction "2_2") (pintype "passive"))
      (node (ref "M1") (pin "4") (pinfunction "4_4") (pintype "passive"))
    )
    (net (code "128") (name "/M1_ENCB") (class "Default")
      (node (ref "JP_S2") (pin "9") (pinfunction "9_9") (pintype "passive"))
      (node (ref "JP_S3") (pin "5") (pinfunction "5_5") (pintype "passive"))
      (node (ref "M1") (pin "5") (pinfunction "5_5") (pintype "passive"))
    )
    (net (code "129") (name "/M1_FWD") (class "Default")
      (node (ref "DRV1") (pin "4") (pinfunction "IN1_4") (pintype "input"))
      (node (ref "JP_S2") (pin "1") (pinfunction "1_1") (pintype "passive"))
      (node (ref "JP_S3") (pin "1") (pinfunction "1_1") (pintype "passive"))
    )
    (net (code "130") (name "/M2_1") (class "Default")
      (node (ref "DRV1") (pin "14") (pinfunction "OUT3_14") (pintype "output"))
      (node (ref "M2") (pin "1") (pinfunction "1_1") (pintype "passive"))
    )
    (net (code "131") (name "/M2_2") (class "Default")
      (node (ref "DRV1") (pin "13") (pinfunction "OUT4_13") (pintype "output"))
      (node (ref "M2") (pin "2") (pinfunction "2_2") (pintype "passive"))
    )
    (net (code "132") (name "/M2_BKWD") (class "Default")
      (node (ref "DRV1") (pin "7") (pinfunction "IN4_7") (pintype "input"))
      (node (ref "JP_S2") (pin "17") (pinfunction "17_17") (pintype "passive"))
      (node (ref "JP_S3") (pin "9") (pinfunction "9_9") (pintype "passive"))
    )
    (net (code "133") (name "/M2_ENCA") (class "Default")
      (node (ref "JP_S2") (pin "13") (pinfunction "13_13") (pintype "passive"))
      (node (ref "JP_S3") (pin "7") (pinfunction "7_7") (pintype "passive"))
      (node (ref "M2") (pin "4") (pinfunction "4_4") (pintype "passive"))
    )
    (net (code "134") (name "/M2_ENCB") (class "Default")
      (node (ref "JP_S2") (pin "19") (pinfunction "19_19") (pintype "passive"))
      (node (ref "JP_S3") (pin "10") (pinfunction "10_10") (pintype "passive"))
      (node (ref "M2") (pin "5") (pinfunction "5_5") (pintype "passive"))
    )
    (net (code "135") (name "/M2_FWD") (class "Default")
      (node (ref "DRV1") (pin "6") (pinfunction "IN3_6") (pintype "input"))
      (node (ref "JP_S2") (pin "11") (pinfunction "11_11") (pintype "passive"))
      (node (ref "JP_S3") (pin "6") (pinfunction "6_6") (pintype "passive"))
    )
    (net (code "136") (name "/M3_1") (class "Default")
      (node (ref "DRV2") (pin "16") (pinfunction "OUT1_16") (pintype "output"))
      (node (ref "M3") (pin "1") (pinfunction "1_1") (pintype "passive"))
    )
    (net (code "137") (name "/M3_2") (class "Default")
      (node (ref "DRV2") (pin "15") (pinfunction "OUT2_15") (pintype "output"))
      (node (ref "M3") (pin "2") (pinfunction "2_2") (pintype "passive"))
    )
    (net (code "138") (name "/M3_BKWD") (class "Default")
      (node (ref "DRV2") (pin "5") (pinfunction "IN2_5") (pintype "input"))
      (node (ref "JP_S2") (pin "27") (pinfunction "27_27") (pintype "passive"))
      (node (ref "JP_S3") (pin "14") (pinfunction "14_14") (pintype "passive"))
    )
    (net (code "139") (name "/M3_ENCA") (class "Default")
      (node (ref "JP_S2") (pin "23") (pinfunction "23_23") (pintype "passive"))
      (node (ref "JP_S3") (pin "12") (pinfunction "12_12") (pintype "passive"))
      (node (ref "M3") (pin "4") (pinfunction "4_4") (pintype "passive"))
    )
    (net (code "140") (name "/M3_ENCB") (class "Default")
      (node (ref "JP_S2") (pin "29") (pinfunction "29_29") (pintype "passive"))
      (node (ref "JP_S3") (pin "15") (pinfunction "15_15") (pintype "passive"))
      (node (ref "M3") (pin "5") (pinfunction "5_5") (pintype "passive"))
    )
    (net (code "141") (name "/M3_FWD") (class "Default")
      (node (ref "DRV2") (pin "4") (pinfunction "IN1_4") (pintype "input"))
      (node (ref "JP_S2") (pin "21") (pinfunction "21_21") (pintype "passive"))
      (node (ref "JP_S3") (pin "11") (pinfunction "11_11") (pintype "passive"))
    )
    (net (code "142") (name "/M4_1") (class "Default")
      (node (ref "DRV2") (pin "14") (pinfunction "OUT3_14") (pintype "output"))
      (node (ref "M4") (pin "1") (pinfunction "1_1") (pintype "passive"))
    )
    (net (code "143") (name "/M4_2") (class "Default")
      (node (ref "DRV2") (pin "13") (pinfunction "OUT4_13") (pintype "output"))
      (node (ref "M4") (pin "2") (pinfunction "2_2") (pintype "passive"))
    )
    (net (code "144") (name "/M4_BKWD") (class "Default")
      (node (ref "DRV2") (pin "7") (pinfunction "IN4_7") (pintype "input"))
      (node (ref "JP_S2") (pin "37") (pinfunction "37_37") (pintype "passive"))
      (node (ref "JP_S3") (pin "19") (pinfunction "19_19") (pintype "passive"))
    )
    (net (code "145") (name "/M4_ENCA") (class "Default")
      (node (ref "JP_S2") (pin "33") (pinfunction "33_33") (pintype "passive"))
      (node (ref "JP_S3") (pin "17") (pinfunction "17_17") (pintype "passive"))
      (node (ref "M4") (pin "4") (pinfunction "4_4") (pintype "passive"))
    )
    (net (code "146") (name "/M4_ENCB") (class "Default")
      (node (ref "JP_S2") (pin "39") (pinfunction "39_39") (pintype "passive"))
      (node (ref "JP_S3") (pin "20") (pinfunction "20_20") (pintype "passive"))
      (node (ref "M4") (pin "5") (pinfunction "5_5") (pintype "passive"))
    )
    (net (code "147") (name "/M4_FWD") (class "Default")
      (node (ref "DRV2") (pin "6") (pinfunction "IN3_6") (pintype "input"))
      (node (ref "JP_S2") (pin "31") (pinfunction "31_31") (pintype "passive"))
      (node (ref "JP_S3") (pin "16") (pinfunction "16_16") (pintype "passive"))
    )
    (net (code "148") (name "/NCS") (class "Default")
      (node (ref "MPU_6500") (pin "17") (pinfunction "17_17") (pintype "passive"))
      (node (ref "MPU_6500") (pin "18") (pinfunction "18_18") (pintype "passive"))
    )
    (net (code "149") (name "/PG_BUCK_MOT") (class "Default")
      (node (ref "BUCK_5V") (pin "1") (pinfunction "PG_1") (pintype "bidirectional"))
    )
    (net (code "150") (name "/PG_BUCK_PI4") (class "Default")
      (node (ref "BUCK_5V1") (pin "1") (pinfunction "PG_1") (pintype "bidirectional"))
    )
    (net (code "151") (name "/RUN") (class "Default")
      (node (ref "JP_D1") (pin "11") (pinfunction "11_11") (pintype "passive"))
      (node (ref "JP_D2") (pin "22") (pinfunction "22_22") (pintype "passive"))
      (node (ref "UC_MOTOARE") (pin "30") (pinfunction "~{RUN}_30") (pintype "input"))
    )
    (net (code "152") (name "/RUN_2") (class "Default")
      (node (ref "JP_D4") (pin "11") (pinfunction "11_11") (pintype "passive"))
      (node (ref "JP_D5") (pin "22") (pinfunction "22_22") (pintype "passive"))
      (node (ref "UC_ULTRASONIC") (pin "30") (pinfunction "~{RUN}_30") (pintype "input"))
    )
    (net (code "153") (name "/RUN_IN") (class "Default")
      (node (ref "JP_D2") (pin "21") (pinfunction "21_21") (pintype "passive"))
      (node (ref "JP_D3") (pin "11") (pinfunction "11_11") (pintype "passive"))
    )
    (net (code "154") (name "/RUN_IN_2") (class "Default")
      (node (ref "JP_D5") (pin "21") (pinfunction "21_21") (pintype "passive"))
      (node (ref "JP_D6") (pin "11") (pinfunction "11_11") (pintype "passive"))
    )
    (net (code "155") (name "/TP1_GND") (class "Default")
      (node (ref "UC_MOTOARE") (pin "TP1") (pinfunction "TP1_GND_TP1") (pintype "power_in"))
    )
    (net (code "156") (name "/TP1_GND_2") (class "Default")
      (node (ref "UC_ULTRASONIC") (pin "TP1") (pinfunction "TP1_GND_TP1") (pintype "power_in"))
    )
    (net (code "157") (name "/TP2") (class "Default")
      (node (ref "UC_MOTOARE") (pin "TP2") (pinfunction "TP2_USB_DM_TP2") (pintype "bidirectional"))
    )
    (net (code "158") (name "/TP2_2") (class "Default")
      (node (ref "UC_ULTRASONIC") (pin "TP2") (pinfunction "TP2_USB_DM_TP2") (pintype "bidirectional"))
    )
    (net (code "159") (name "/TP3") (class "Default")
      (node (ref "UC_MOTOARE") (pin "TP3") (pinfunction "TP3_USB_DP_TP3") (pintype "bidirectional"))
    )
    (net (code "160") (name "/TP3_2") (class "Default")
      (node (ref "UC_ULTRASONIC") (pin "TP3") (pinfunction "TP3_USB_DP_TP3") (pintype "bidirectional"))
    )
    (net (code "161") (name "/TP5") (class "Default")
      (node (ref "UC_MOTOARE") (pin "TP5") (pinfunction "TP5_GPIO25/LED_TP5") (pintype "output"))
    )
    (net (code "162") (name "/TP5_2") (class "Default")
      (node (ref "UC_ULTRASONIC") (pin "TP5") (pinfunction "TP5_GPIO25/LED_TP5") (pintype "output"))
    )
    (net (code "163") (name "/TP6") (class "Default")
      (node (ref "UC_MOTOARE") (pin "TP6") (pinfunction "TP6_BOOTSEL_TP6") (pintype "input"))
    )
    (net (code "164") (name "/TP6_2") (class "Default")
      (node (ref "UC_ULTRASONIC") (pin "TP6") (pinfunction "TP6_BOOTSEL_TP6") (pintype "input"))
    )
    (net (code "165") (name "/UART0_RX") (class "Default")
      (node (ref "JP_D2") (pin "37") (pinfunction "37_37") (pintype "passive"))
      (node (ref "JP_D3") (pin "19") (pinfunction "19_19") (pintype "passive"))
    )
    (net (code "166") (name "/UART0_RX_2") (class "Default")
      (node (ref "JP_D5") (pin "37") (pinfunction "37_37") (pintype "passive"))
      (node (ref "JP_D6") (pin "19") (pinfunction "19_19") (pintype "passive"))
    )
    (net (code "167") (name "/UART0_TX") (class "Default")
      (node (ref "JP_D2") (pin "39") (pinfunction "39_39") (pintype "passive"))
      (node (ref "JP_D3") (pin "20") (pinfunction "20_20") (pintype "passive"))
    )
    (net (code "168") (name "/UART0_TX_2") (class "Default")
      (node (ref "JP_D5") (pin "39") (pinfunction "39_39") (pintype "passive"))
      (node (ref "JP_D6") (pin "20") (pinfunction "20_20") (pintype "passive"))
    )
    (net (code "169") (name "/VBAT_11") (class "Default")
      (node (ref "11V_BATTERY_PI4") (pin "P") (pinfunction "POS_P") (pintype "passive"))
      (node (ref "11_1V_BATTERY_SENZ") (pin "P") (pinfunction "POS_P") (pintype "passive"))
      (node (ref "BUCK_5V1") (pin "3") (pinfunction "VIN_3") (pintype "bidirectional"))
      (node (ref "R17") (pin "2") (pinfunction "2_2") (pintype "passive"))
    )
    (net (code "170") (name "/VBAT_14_8") (class "Default")
      (node (ref "14_8V_BATTERY") (pin "P") (pinfunction "POS_P") (pintype "passive"))
      (node (ref "BUCK_5V") (pin "3") (pinfunction "VIN_3") (pintype "bidirectional"))
      (node (ref "DRV1") (pin "10") (pinfunction "VIN_10") (pintype "power_in"))
      (node (ref "DRV2") (pin "10") (pinfunction "VIN_10") (pintype "power_in"))
      (node (ref "R15") (pin "2") (pinfunction "2_2") (pintype "passive"))
    )
    (net (code "171") (name "/VBB1") (class "Default")
      (node (ref "DRV1") (pin "11") (pinfunction "VBB_11") (pintype "bidirectional"))
    )
    (net (code "172") (name "/VBB2") (class "Default")
      (node (ref "DRV2") (pin "11") (pinfunction "VBB_11") (pintype "bidirectional"))
    )
    (net (code "173") (name "/VBUS") (class "Default")
      (node (ref "JP_D1") (pin "1") (pinfunction "1_1") (pintype "passive"))
      (node (ref "JP_D2") (pin "2") (pinfunction "2_2") (pintype "passive"))
      (node (ref "UC_MOTOARE") (pin "40") (pinfunction "VBUS_40") (pintype "power_in"))
    )
    (net (code "174") (name "/VBUS_2") (class "Default")
      (node (ref "JP_D4") (pin "1") (pinfunction "1_1") (pintype "passive"))
      (node (ref "JP_D5") (pin "2") (pinfunction "2_2") (pintype "passive"))
      (node (ref "UC_ULTRASONIC") (pin "40") (pinfunction "VBUS_40") (pintype "power_in"))
    )
    (net (code "175") (name "/VBUS_OUT") (class "Default")
      (node (ref "JP_D2") (pin "1") (pinfunction "1_1") (pintype "passive"))
      (node (ref "JP_D3") (pin "1") (pinfunction "1_1") (pintype "passive"))
    )
    (net (code "176") (name "/VBUS_OUT_2") (class "Default")
      (node (ref "JP_D5") (pin "1") (pinfunction "1_1") (pintype "passive"))
      (node (ref "JP_D6") (pin "1") (pinfunction "1_1") (pintype "passive"))
    )
    (net (code "177") (name "/VSYS") (class "Default")
      (node (ref "JP_D1") (pin "2") (pinfunction "2_2") (pintype "passive"))
      (node (ref "JP_D2") (pin "4") (pinfunction "4_4") (pintype "passive"))
      (node (ref "UC_MOTOARE") (pin "39") (pinfunction "VSYS_39") (pintype "power_in"))
    )
    (net (code "178") (name "/VSYS_2") (class "Default")
      (node (ref "JP_D4") (pin "2") (pinfunction "2_2") (pintype "passive"))
      (node (ref "JP_D5") (pin "4") (pinfunction "4_4") (pintype "passive"))
      (node (ref "UC_ULTRASONIC") (pin "39") (pinfunction "VSYS_39") (pintype "power_in"))
    )
    (net (code "179") (name "GND") (class "Default")
      (node (ref "11V_BATTERY_PI4") (pin "N") (pinfunction "NEG_N") (pintype "passive"))
      (node (ref "11_1V_BATTERY_SENZ") (pin "N") (pinfunction "NEG_N") (pintype "passive"))
      (node (ref "14_8V_BATTERY") (pin "N") (pinfunction "NEG_N") (pintype "passive"))
      (node (ref "5V_PI4_SUPPLY") (pin "N") (pinfunction "NEG_N") (pintype "passive"))
      (node (ref "BUCK_5V") (pin "4") (pinfunction "GND__4") (pintype "bidirectional"))
      (node (ref "BUCK_5V") (pin "6") (pinfunction "GND_6") (pintype "bidirectional"))
      (node (ref "BUCK_5V1") (pin "4") (pinfunction "GND__4") (pintype "bidirectional"))
      (node (ref "BUCK_5V1") (pin "6") (pinfunction "GND_6") (pintype "bidirectional"))
      (node (ref "DRV1") (pin "12") (pinfunction "GND2_12") (pintype "bidirectional"))
      (node (ref "DRV1") (pin "8") (pinfunction "GND_8") (pintype "power_in"))
      (node (ref "DRV1") (pin "9") (pinfunction "GND1_9") (pintype "power_in"))
      (node (ref "DRV2") (pin "12") (pinfunction "GND2_12") (pintype "bidirectional"))
      (node (ref "DRV2") (pin "8") (pinfunction "GND_8") (pintype "power_in"))
      (node (ref "DRV2") (pin "9") (pinfunction "GND1_9") (pintype "power_in"))
      (node (ref "JP_D1") (pin "13") (pinfunction "13_13") (pintype "passive"))
      (node (ref "JP_D1") (pin "18") (pinfunction "18_18") (pintype "passive"))
      (node (ref "JP_D1") (pin "3") (pinfunction "3_3") (pintype "passive"))
      (node (ref "JP_D2") (pin "15") (pinfunction "15_15") (pintype "passive"))
      (node (ref "JP_D2") (pin "25") (pinfunction "25_25") (pintype "passive"))
      (node (ref "JP_D2") (pin "26") (pinfunction "26_26") (pintype "passive"))
      (node (ref "JP_D2") (pin "35") (pinfunction "35_35") (pintype "passive"))
      (node (ref "JP_D2") (pin "36") (pinfunction "36_36") (pintype "passive"))
      (node (ref "JP_D2") (pin "5") (pinfunction "5_5") (pintype "passive"))
      (node (ref "JP_D2") (pin "6") (pinfunction "6_6") (pintype "passive"))
      (node (ref "JP_D3") (pin "13") (pinfunction "13_13") (pintype "passive"))
      (node (ref "JP_D3") (pin "18") (pinfunction "18_18") (pintype "passive"))
      (node (ref "JP_D3") (pin "3") (pinfunction "3_3") (pintype "passive"))
      (node (ref "JP_D3") (pin "8") (pinfunction "8_8") (pintype "passive"))
      (node (ref "JP_D4") (pin "13") (pinfunction "13_13") (pintype "passive"))
      (node (ref "JP_D4") (pin "18") (pinfunction "18_18") (pintype "passive"))
      (node (ref "JP_D4") (pin "3") (pinfunction "3_3") (pintype "passive"))
      (node (ref "JP_D5") (pin "15") (pinfunction "15_15") (pintype "passive"))
      (node (ref "JP_D5") (pin "25") (pinfunction "25_25") (pintype "passive"))
      (node (ref "JP_D5") (pin "26") (pinfunction "26_26") (pintype "passive"))
      (node (ref "JP_D5") (pin "35") (pinfunction "35_35") (pintype "passive"))
      (node (ref "JP_D5") (pin "36") (pinfunction "36_36") (pintype "passive"))
      (node (ref "JP_D5") (pin "5") (pinfunction "5_5") (pintype "passive"))
      (node (ref "JP_D5") (pin "6") (pinfunction "6_6") (pintype "passive"))
      (node (ref "JP_D6") (pin "13") (pinfunction "13_13") (pintype "passive"))
      (node (ref "JP_D6") (pin "18") (pinfunction "18_18") (pintype "passive"))
      (node (ref "JP_D6") (pin "3") (pinfunction "3_3") (pintype "passive"))
      (node (ref "JP_D6") (pin "8") (pinfunction "8_8") (pintype "passive"))
      (node (ref "JP_S1") (pin "13") (pinfunction "13_13") (pintype "passive"))
      (node (ref "JP_S1") (pin "18") (pinfunction "18_18") (pintype "passive"))
      (node (ref "JP_S1") (pin "3") (pinfunction "3_3") (pintype "passive"))
      (node (ref "JP_S1") (pin "8") (pinfunction "8_8") (pintype "passive"))
      (node (ref "JP_S2") (pin "15") (pinfunction "15_15") (pintype "passive"))
      (node (ref "JP_S2") (pin "16") (pinfunction "16_16") (pintype "passive"))
      (node (ref "JP_S2") (pin "25") (pinfunction "25_25") (pintype "passive"))
      (node (ref "JP_S2") (pin "26") (pinfunction "26_26") (pintype "passive"))
      (node (ref "JP_S2") (pin "35") (pinfunction "35_35") (pintype "passive"))
      (node (ref "JP_S2") (pin "36") (pinfunction "36_36") (pintype "passive"))
      (node (ref "JP_S2") (pin "5") (pinfunction "5_5") (pintype "passive"))
      (node (ref "JP_S2") (pin "6") (pinfunction "6_6") (pintype "passive"))
      (node (ref "JP_S3") (pin "13") (pinfunction "13_13") (pintype "passive"))
      (node (ref "JP_S3") (pin "18") (pinfunction "18_18") (pintype "passive"))
      (node (ref "JP_S3") (pin "3") (pinfunction "3_3") (pintype "passive"))
      (node (ref "JP_S3") (pin "8") (pinfunction "8_8") (pintype "passive"))
      (node (ref "JP_S4") (pin "13") (pinfunction "13_13") (pintype "passive"))
      (node (ref "JP_S4") (pin "18") (pinfunction "18_18") (pintype "passive"))
      (node (ref "JP_S4") (pin "3") (pinfunction "3_3") (pintype "passive"))
      (node (ref "JP_S4") (pin "8") (pinfunction "8_8") (pintype "passive"))
      (node (ref "JP_S5") (pin "15") (pinfunction "15_15") (pintype "passive"))
      (node (ref "JP_S5") (pin "16") (pinfunction "16_16") (pintype "passive"))
      (node (ref "JP_S5") (pin "25") (pinfunction "25_25") (pintype "passive"))
      (node (ref "JP_S5") (pin "26") (pinfunction "26_26") (pintype "passive"))
      (node (ref "JP_S5") (pin "35") (pinfunction "35_35") (pintype "passive"))
      (node (ref "JP_S5") (pin "36") (pinfunction "36_36") (pintype "passive"))
      (node (ref "JP_S5") (pin "5") (pinfunction "5_5") (pintype "passive"))
      (node (ref "JP_S5") (pin "6") (pinfunction "6_6") (pintype "passive"))
      (node (ref "JP_S6") (pin "13") (pinfunction "13_13") (pintype "passive"))
      (node (ref "JP_S6") (pin "18") (pinfunction "18_18") (pintype "passive"))
      (node (ref "JP_S6") (pin "3") (pinfunction "3_3") (pintype "passive"))
      (node (ref "JP_S6") (pin "8") (pinfunction "8_8") (pintype "passive"))
      (node (ref "M1") (pin "6") (pinfunction "6_6") (pintype "passive"))
      (node (ref "M2") (pin "6") (pinfunction "6_6") (pintype "passive"))
      (node (ref "M3") (pin "6") (pinfunction "6_6") (pintype "passive"))
      (node (ref "M4") (pin "6") (pinfunction "6_6") (pintype "passive"))
      (node (ref "R1") (pin "1") (pinfunction "1_1") (pintype "passive"))
      (node (ref "R11") (pin "1") (pinfunction "1_1") (pintype "passive"))
      (node (ref "R13") (pin "1") (pinfunction "1_1") (pintype "passive"))
      (node (ref "R19") (pin "1") (pinfunction "1_1") (pintype "passive"))
      (node (ref "R20") (pin "1") (pinfunction "1_1") (pintype "passive"))
      (node (ref "R3") (pin "1") (pinfunction "1_1") (pintype "passive"))
      (node (ref "R5") (pin "1") (pinfunction "1_1") (pintype "passive"))
      (node (ref "R7") (pin "1") (pinfunction "1_1") (pintype "passive"))
      (node (ref "R9") (pin "1") (pinfunction "1_1") (pintype "passive"))
      (node (ref "U$1") (pin "11") (pinfunction "GND2_11") (pintype "bidirectional"))
      (node (ref "U$1") (pin "2") (pinfunction "GND1_2") (pintype "bidirectional"))
      (node (ref "U$10") (pin "2") (pinfunction "S_2") (pintype "bidirectional"))
      (node (ref "U$11") (pin "2") (pinfunction "S_2") (pintype "bidirectional"))
      (node (ref "U$12") (pin "2") (pinfunction "S_2") (pintype "bidirectional"))
      (node (ref "U$13") (pin "2") (pinfunction "S_2") (pintype "bidirectional"))
      (node (ref "U$14") (pin "2") (pinfunction "S_2") (pintype "bidirectional"))
      (node (ref "U$2") (pin "11") (pinfunction "GND2_11") (pintype "bidirectional"))
      (node (ref "U$2") (pin "2") (pinfunction "GND1_2") (pintype "bidirectional"))
      (node (ref "U$8") (pin "2") (pinfunction "S_2") (pintype "bidirectional"))
      (node (ref "U$9") (pin "2") (pinfunction "S_2") (pintype "bidirectional"))
      (node (ref "UC_MOTOARE") (pin "13") (pinfunction "GND_13") (pintype "power_in"))
      (node (ref "UC_MOTOARE") (pin "18") (pinfunction "GND_18") (pintype "power_in"))
      (node (ref "UC_MOTOARE") (pin "23") (pinfunction "GND_23") (pintype "power_in"))
      (node (ref "UC_MOTOARE") (pin "28") (pinfunction "GND_28") (pintype "power_in"))
      (node (ref "UC_MOTOARE") (pin "3") (pinfunction "GND_3") (pintype "power_in"))
      (node (ref "UC_MOTOARE") (pin "38") (pinfunction "GND_38") (pintype "power_in"))
      (node (ref "UC_MOTOARE") (pin "8") (pinfunction "GND_8") (pintype "power_in"))
      (node (ref "UC_MOTOARE") (pin "D2") (pinfunction "GND_D2") (pintype "power_in"))
      (node (ref "UC_ULTRASONIC") (pin "13") (pinfunction "GND_13") (pintype "power_in"))
      (node (ref "UC_ULTRASONIC") (pin "18") (pinfunction "GND_18") (pintype "power_in"))
      (node (ref "UC_ULTRASONIC") (pin "23") (pinfunction "GND_23") (pintype "power_in"))
      (node (ref "UC_ULTRASONIC") (pin "28") (pinfunction "GND_28") (pintype "power_in"))
      (node (ref "UC_ULTRASONIC") (pin "3") (pinfunction "GND_3") (pintype "power_in"))
      (node (ref "UC_ULTRASONIC") (pin "38") (pinfunction "GND_38") (pintype "power_in"))
      (node (ref "UC_ULTRASONIC") (pin "8") (pinfunction "GND_8") (pintype "power_in"))
      (node (ref "UC_ULTRASONIC") (pin "D2") (pinfunction "GND_D2") (pintype "power_in"))
    )
    (net (code "180") (name "Net-(R16-Pad1)") (class "Default")
      (node (ref "R16") (pin "1") (pinfunction "1_1") (pintype "passive"))
      (node (ref "R19") (pin "2") (pinfunction "2_2") (pintype "passive"))
    )
    (net (code "181") (name "Net-(R18-Pad1)") (class "Default")
      (node (ref "R18") (pin "1") (pinfunction "1_1") (pintype "passive"))
      (node (ref "R20") (pin "2") (pinfunction "2_2") (pintype "passive"))
    )
    (net (code "182") (name "Net-(U$8-D)") (class "Default")
      (node (ref "MPU_6500") (pin "3") (pinfunction "3_3") (pintype "passive"))
      (node (ref "MPU_6500") (pin "4") (pinfunction "4_4") (pintype "passive"))
      (node (ref "U$8") (pin "3") (pinfunction "D_3") (pintype "bidirectional"))
    )
    (net (code "183") (name "Net-(U$8-G)") (class "Default")
      (node (ref "R13") (pin "2") (pinfunction "2_2") (pintype "passive"))
      (node (ref "R14") (pin "1") (pinfunction "1_1") (pintype "passive"))
      (node (ref "U$8") (pin "1") (pinfunction "G_1") (pintype "bidirectional"))
    )
    (net (code "184") (name "Net-(U$9-D)") (class "Default")
      (node (ref "HC_SR04_1") (pin "4") (pinfunction "4_4") (pintype "passive"))
      (node (ref "U$9") (pin "3") (pinfunction "D_3") (pintype "bidirectional"))
    )
    (net (code "185") (name "Net-(U$9-G)") (class "Default")
      (node (ref "R3") (pin "2") (pinfunction "2_2") (pintype "passive"))
      (node (ref "R4") (pin "2") (pinfunction "2_2") (pintype "passive"))
      (node (ref "U$9") (pin "1") (pinfunction "G_1") (pintype "bidirectional"))
    )
    (net (code "186") (name "Net-(U$10-D)") (class "Default")
      (node (ref "HC_SR04_2") (pin "4") (pinfunction "4_4") (pintype "passive"))
      (node (ref "HC_SR04_3") (pin "4") (pinfunction "4_4") (pintype "passive"))
      (node (ref "U$10") (pin "3") (pinfunction "D_3") (pintype "bidirectional"))
    )
    (net (code "187") (name "Net-(U$10-G)") (class "Default")
      (node (ref "R1") (pin "2") (pinfunction "2_2") (pintype "passive"))
      (node (ref "R2") (pin "2") (pinfunction "2_2") (pintype "passive"))
      (node (ref "U$10") (pin "1") (pinfunction "G_1") (pintype "bidirectional"))
    )
    (net (code "188") (name "Net-(U$11-D)") (class "Default")
      (node (ref "HC_SR04_4") (pin "4") (pinfunction "4_4") (pintype "passive"))
      (node (ref "U$11") (pin "3") (pinfunction "D_3") (pintype "bidirectional"))
    )
    (net (code "189") (name "Net-(U$11-G)") (class "Default")
      (node (ref "R5") (pin "2") (pinfunction "2_2") (pintype "passive"))
      (node (ref "R6") (pin "2") (pinfunction "2_2") (pintype "passive"))
      (node (ref "U$11") (pin "1") (pinfunction "G_1") (pintype "bidirectional"))
    )
    (net (code "190") (name "Net-(U$12-D)") (class "Default")
      (node (ref "HC_SR04_5") (pin "4") (pinfunction "4_4") (pintype "passive"))
      (node (ref "U$12") (pin "3") (pinfunction "D_3") (pintype "bidirectional"))
    )
    (net (code "191") (name "Net-(U$12-G)") (class "Default")
      (node (ref "R11") (pin "2") (pinfunction "2_2") (pintype "passive"))
      (node (ref "R12") (pin "2") (pinfunction "2_2") (pintype "passive"))
      (node (ref "U$12") (pin "1") (pinfunction "G_1") (pintype "bidirectional"))
    )
    (net (code "192") (name "Net-(U$13-D)") (class "Default")
      (node (ref "HC_SR04_6") (pin "4") (pinfunction "4_4") (pintype "passive"))
      (node (ref "HC_SR04_7") (pin "4") (pinfunction "4_4") (pintype "passive"))
      (node (ref "U$13") (pin "3") (pinfunction "D_3") (pintype "bidirectional"))
    )
    (net (code "193") (name "Net-(U$13-G)") (class "Default")
      (node (ref "R7") (pin "2") (pinfunction "2_2") (pintype "passive"))
      (node (ref "R8") (pin "2") (pinfunction "2_2") (pintype "passive"))
      (node (ref "U$13") (pin "1") (pinfunction "G_1") (pintype "bidirectional"))
    )
    (net (code "194") (name "Net-(U$14-D)") (class "Default")
      (node (ref "HC_SR04_8") (pin "4") (pinfunction "4_4") (pintype "passive"))
      (node (ref "U$14") (pin "3") (pinfunction "D_3") (pintype "bidirectional"))
    )
    (net (code "195") (name "Net-(U$14-G)") (class "Default")
      (node (ref "R10") (pin "2") (pinfunction "2_2") (pintype "passive"))
      (node (ref "R9") (pin "2") (pinfunction "2_2") (pintype "passive"))
      (node (ref "U$14") (pin "1") (pinfunction "G_1") (pintype "bidirectional"))
    )
    (net (code "196") (name "unconnected-(UC_MOTOARE-TP4_GPIO23{slash}SMPS_PS-PadTP4)") (class "Default")
      (node (ref "UC_MOTOARE") (pin "TP4") (pinfunction "TP4_GPIO23/SMPS_PS_TP4") (pintype "no_connect"))
    )
    (net (code "197") (name "unconnected-(UC_ULTRASONIC-TP4_GPIO23{slash}SMPS_PS-PadTP4)") (class "Default")
      (node (ref "UC_ULTRASONIC") (pin "TP4") (pinfunction "TP4_GPIO23/SMPS_PS_TP4") (pintype "no_connect"))
    )
  )
)
